# SCH___2021-08-07.net
KiCad netlist of a schematic drawn in EasyEDA
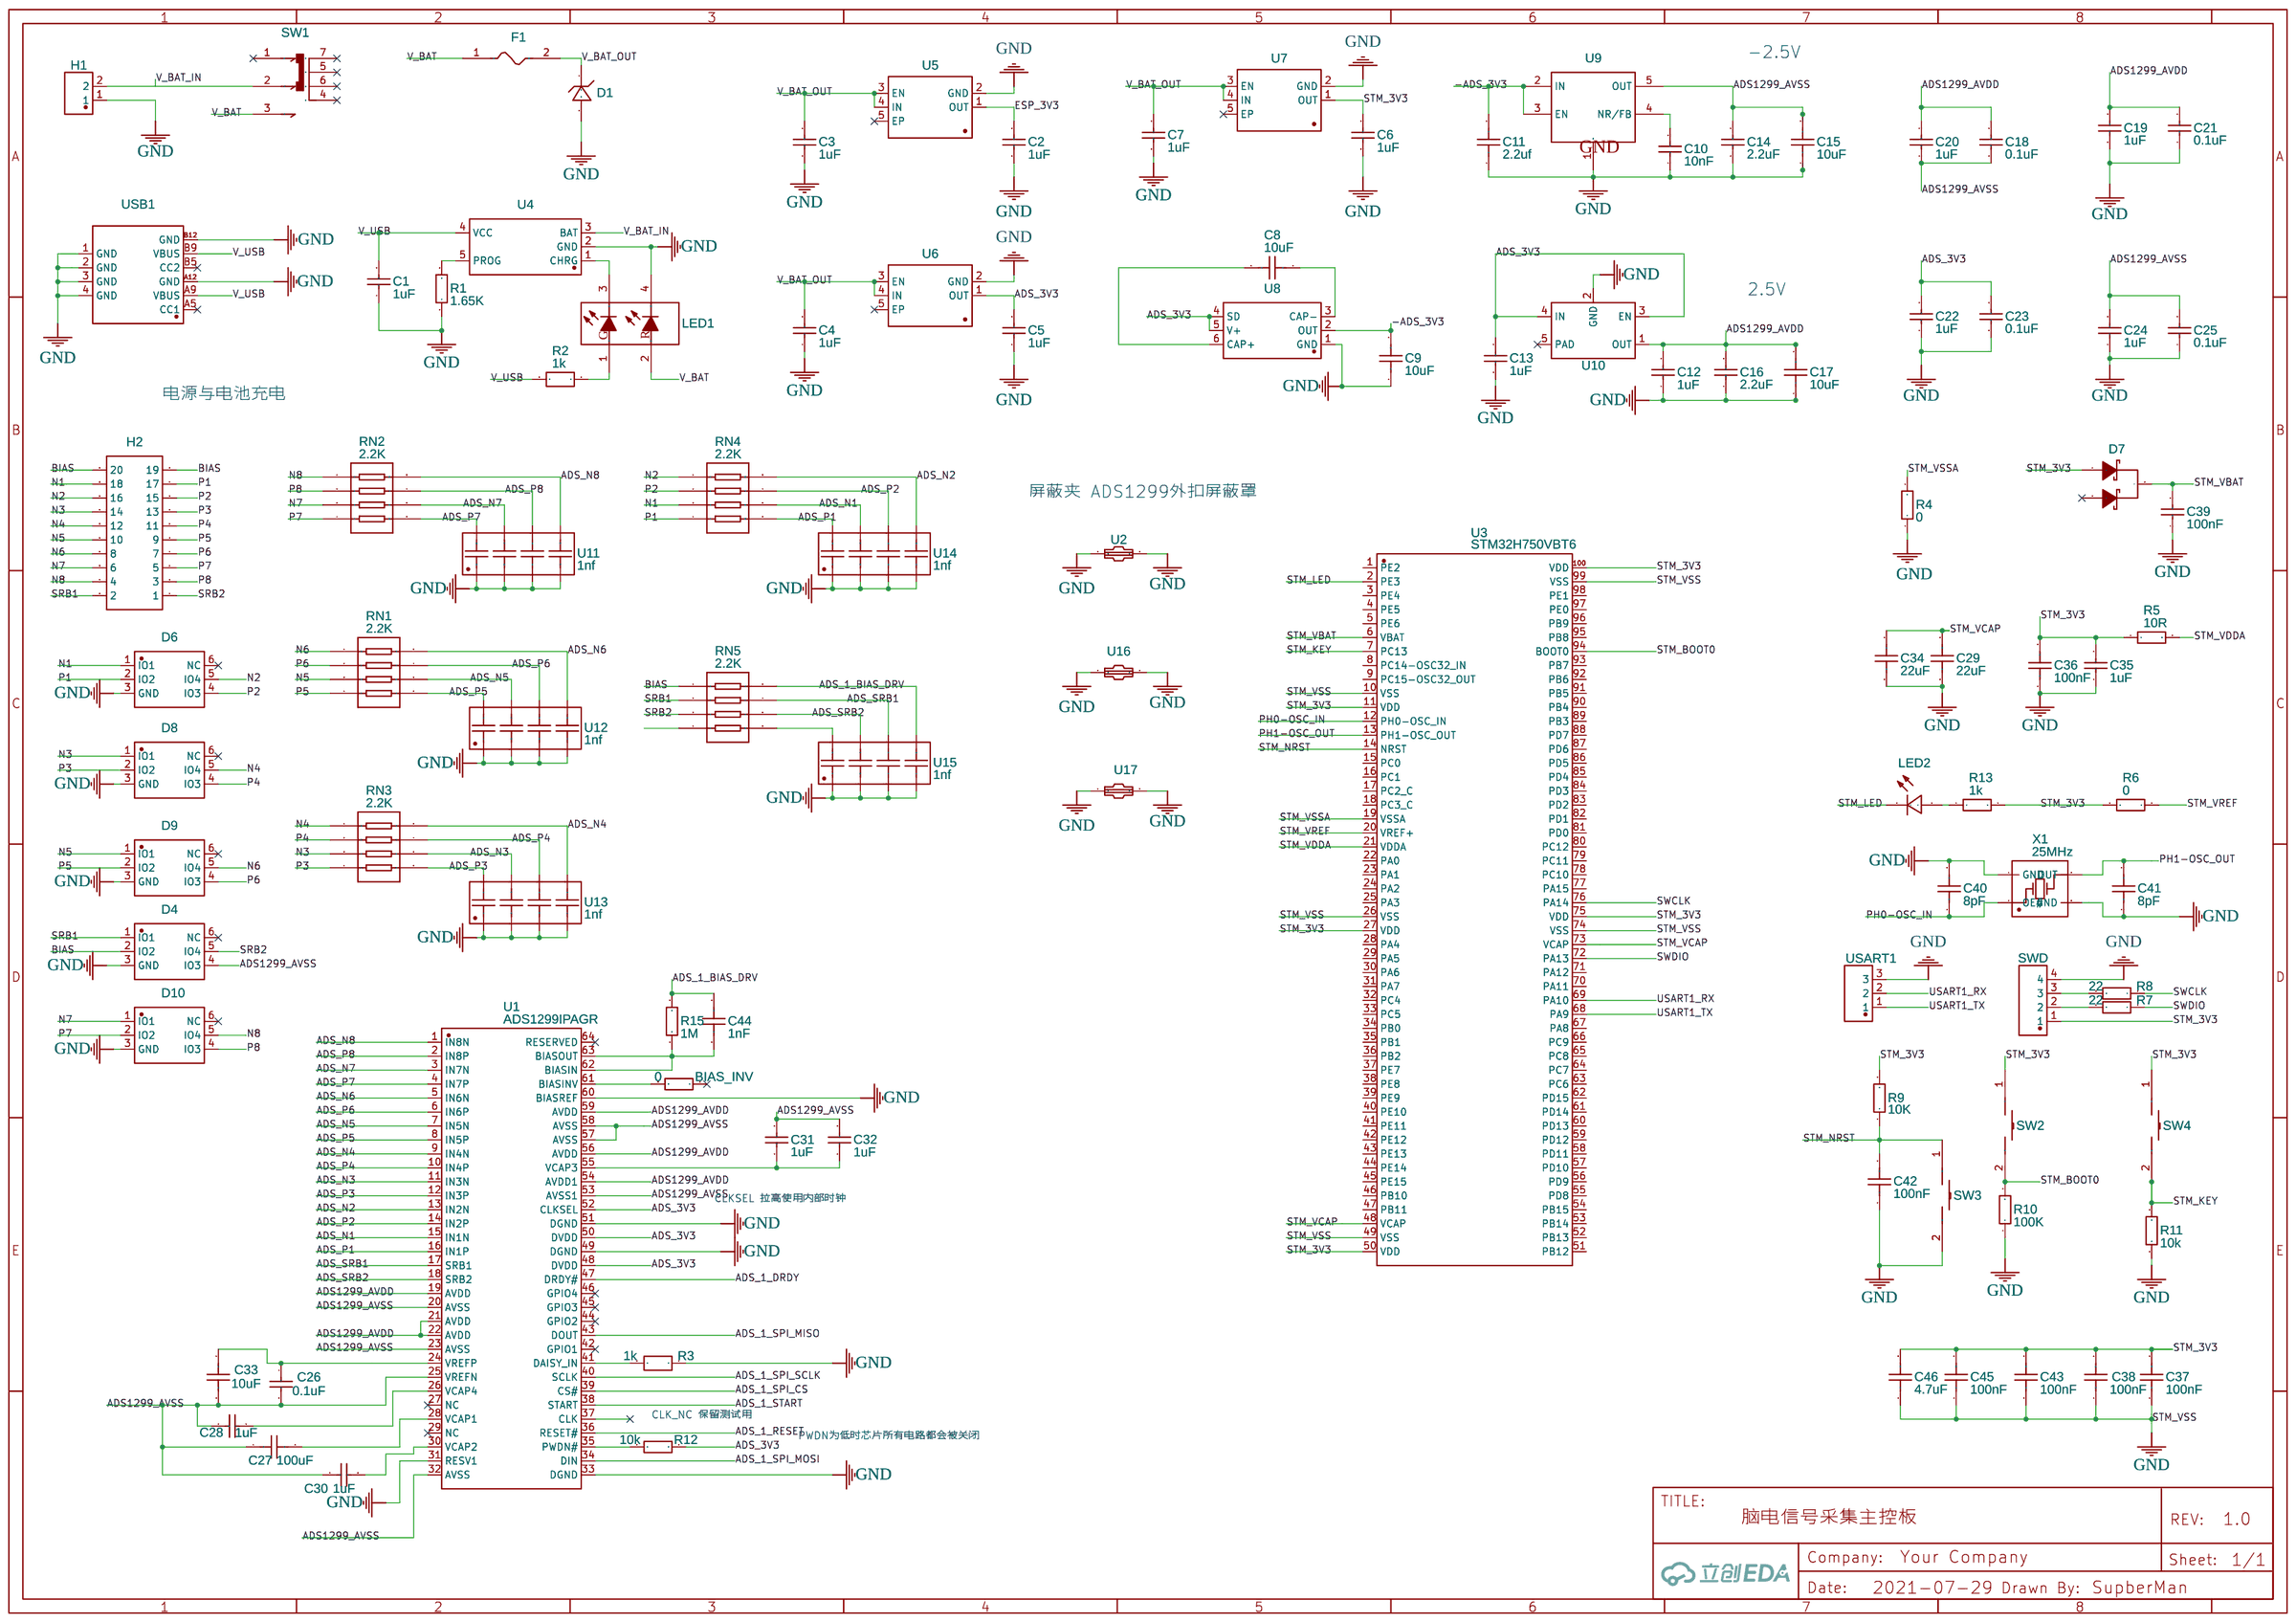
[diagram p0: schematic sheet]

(export (version "E")
  (design (tool "Eeschema 10.0.6"))
  (components
    (comp (ref "BIAS_INV")
      (value "0")
      (fields
        (field (name "BOM_Manufacturer Part") "0402WGJ0000TCE")
        (field (name "BOM_Supplier Part") "C21376")
      )
      (libsource (lib "") (part "0402WGJ0000TCE_3"))
    )
    (comp (ref "C1")
      (value "1uF")
      (fields
        (field (name "BOM_Manufacturer Part") "0603F105M160NT")
        (field (name "BOM_Supplier Part") "C1689")
      )
      (libsource (lib "") (part "0603F105M160NT"))
    )
    (comp (ref "C2")
      (value "1uF")
      (fields
        (field (name "BOM_Manufacturer Part") "0402B105K100NT")
        (field (name "BOM_Supplier Part") "C1526")
      )
      (libsource (lib "") (part "0402B105K100NT"))
    )
    (comp (ref "C3")
      (value "1uF")
      (fields
        (field (name "BOM_Manufacturer Part") "0603F105M160NT")
        (field (name "BOM_Supplier Part") "C1689")
      )
      (libsource (lib "") (part "0603F105M160NT"))
    )
    (comp (ref "C4")
      (value "1uF")
      (fields
        (field (name "BOM_Manufacturer Part") "0603F105M160NT")
        (field (name "BOM_Supplier Part") "C1689")
      )
      (libsource (lib "") (part "0603F105M160NT"))
    )
    (comp (ref "C5")
      (value "1uF")
      (fields
        (field (name "BOM_Manufacturer Part") "0402B105K100NT")
        (field (name "BOM_Supplier Part") "C1526")
      )
      (libsource (lib "") (part "0402B105K100NT"))
    )
    (comp (ref "C6")
      (value "1uF")
      (fields
        (field (name "BOM_Manufacturer Part") "0402B105K100NT")
        (field (name "BOM_Supplier Part") "C1526")
      )
      (libsource (lib "") (part "0402B105K100NT"))
    )
    (comp (ref "C7")
      (value "1uF")
      (fields
        (field (name "BOM_Manufacturer Part") "0603F105M160NT")
        (field (name "BOM_Supplier Part") "C1689")
      )
      (libsource (lib "") (part "0603F105M160NT"))
    )
    (comp (ref "C8")
      (value "10uF")
      (fields
        (field (name "BOM_Manufacturer Part") "GRT188R61E106ME13D")
        (field (name "BOM_Supplier Part") "C697423")
      )
      (libsource (lib "") (part "GRT188R61E106ME13D_1"))
    )
    (comp (ref "C9")
      (value "10uF")
      (fields
        (field (name "BOM_Manufacturer Part") "GRT188R61E106ME13D")
        (field (name "BOM_Supplier Part") "C697423")
      )
      (libsource (lib "") (part "GRT188R61E106ME13D"))
    )
    (comp (ref "C10")
      (value "10nF")
      (fields
        (field (name "BOM_Manufacturer Part") "0402B103K500NT")
        (field (name "BOM_Supplier Part") "C1524")
      )
      (libsource (lib "") (part "0402B103K500NT_1"))
    )
    (comp (ref "C11")
      (value "2.2uf")
      (fields
        (field (name "BOM_Manufacturer Part") "EMK105CC6225KV-F")
        (field (name "BOM_Supplier Part") "C697612")
      )
      (libsource (lib "") (part "EMK105CC6225KV-F"))
    )
    (comp (ref "C12")
      (value "1uF")
      (fields
        (field (name "BOM_Manufacturer Part") "0402B105K100NT")
        (field (name "BOM_Supplier Part") "C1526")
      )
      (libsource (lib "") (part "0402B105K100NT"))
    )
    (comp (ref "C13")
      (value "1uF")
      (fields
        (field (name "BOM_Manufacturer Part") "0402B105K100NT")
        (field (name "BOM_Supplier Part") "C1526")
      )
      (libsource (lib "") (part "0402B105K100NT"))
    )
    (comp (ref "C14")
      (value "2.2uF")
      (fields
        (field (name "BOM_Manufacturer Part") "0402B103K500NT")
        (field (name "BOM_Supplier Part") "C1524")
      )
      (libsource (lib "") (part "0402B103K500NT_1"))
    )
    (comp (ref "C15")
      (value "10uF")
      (fields
        (field (name "BOM_Manufacturer Part") "GRT188R61E106ME13D")
        (field (name "BOM_Supplier Part") "C697423")
      )
      (libsource (lib "") (part "GRT188R61E106ME13D"))
    )
    (comp (ref "C16")
      (value "2.2uF")
      (fields
        (field (name "BOM_Manufacturer Part") "0402B103K500NT")
        (field (name "BOM_Supplier Part") "C1524")
      )
      (libsource (lib "") (part "0402B103K500NT_1"))
    )
    (comp (ref "C17")
      (value "10uF")
      (fields
        (field (name "BOM_Manufacturer Part") "GRT188R61E106ME13D")
        (field (name "BOM_Supplier Part") "C697423")
      )
      (libsource (lib "") (part "GRT188R61E106ME13D"))
    )
    (comp (ref "C18")
      (value "0.1uF")
      (fields
        (field (name "BOM_Manufacturer Part") "0402B103K500NT")
        (field (name "BOM_Supplier Part") "C1524")
      )
      (libsource (lib "") (part "0402B103K500NT_1"))
    )
    (comp (ref "C19")
      (value "1uF")
      (fields
        (field (name "BOM_Manufacturer Part") "0402B103K500NT")
        (field (name "BOM_Supplier Part") "C1524")
      )
      (libsource (lib "") (part "0402B103K500NT_1"))
    )
    (comp (ref "C20")
      (value "1uF")
      (fields
        (field (name "BOM_Manufacturer Part") "0402B103K500NT")
        (field (name "BOM_Supplier Part") "C1524")
      )
      (libsource (lib "") (part "0402B103K500NT_1"))
    )
    (comp (ref "C21")
      (value "0.1uF")
      (fields
        (field (name "BOM_Manufacturer Part") "0402B103K500NT")
        (field (name "BOM_Supplier Part") "C1524")
      )
      (libsource (lib "") (part "0402B103K500NT_1"))
    )
    (comp (ref "C22")
      (value "1uF")
      (fields
        (field (name "BOM_Manufacturer Part") "0402B103K500NT")
        (field (name "BOM_Supplier Part") "C1524")
      )
      (libsource (lib "") (part "0402B103K500NT_1"))
    )
    (comp (ref "C23")
      (value "0.1uF")
      (fields
        (field (name "BOM_Manufacturer Part") "0402B103K500NT")
        (field (name "BOM_Supplier Part") "C1524")
      )
      (libsource (lib "") (part "0402B103K500NT_1"))
    )
    (comp (ref "C24")
      (value "1uF")
      (fields
        (field (name "BOM_Manufacturer Part") "0402B103K500NT")
        (field (name "BOM_Supplier Part") "C1524")
      )
      (libsource (lib "") (part "0402B103K500NT_1"))
    )
    (comp (ref "C25")
      (value "0.1uF")
      (fields
        (field (name "BOM_Manufacturer Part") "0402B103K500NT")
        (field (name "BOM_Supplier Part") "C1524")
      )
      (libsource (lib "") (part "0402B103K500NT_1"))
    )
    (comp (ref "C26")
      (value "0.1uF")
      (fields
        (field (name "BOM_Manufacturer Part") "0402B103K500NT")
        (field (name "BOM_Supplier Part") "C1524")
      )
      (libsource (lib "") (part "0402B103K500NT"))
    )
    (comp (ref "C27")
      (value "100uF")
      (fields
        (field (name "BOM_Manufacturer Part") "1210X107M6R3CT")
        (field (name "BOM_Supplier Part") "C509278")
      )
      (libsource (lib "") (part "1210X107M6R3CT"))
    )
    (comp (ref "C28")
      (value "1uF")
      (fields
        (field (name "BOM_Manufacturer Part") "0402B103K500NT")
        (field (name "BOM_Supplier Part") "C1524")
      )
      (libsource (lib "") (part "0402B103K500NT_2"))
    )
    (comp (ref "C29")
      (value "22uF")
      (fields
        (field (name "BOM_Manufacturer Part") "GRM155R60J226ME11D")
        (field (name "BOM_Supplier Part") "C415703")
      )
      (libsource (lib "") (part "GRM155R60J226ME11D"))
    )
    (comp (ref "C30")
      (value "1uF")
      (fields
        (field (name "BOM_Manufacturer Part") "0402B103K500NT")
        (field (name "BOM_Supplier Part") "C1524")
      )
      (libsource (lib "") (part "0402B103K500NT_2"))
    )
    (comp (ref "C31")
      (value "1uF")
      (fields
        (field (name "BOM_Manufacturer Part") "0402B103K500NT")
        (field (name "BOM_Supplier Part") "C1524")
      )
      (libsource (lib "") (part "0402B103K500NT_1"))
    )
    (comp (ref "C32")
      (value "1uF")
      (fields
        (field (name "BOM_Manufacturer Part") "0402B103K500NT")
        (field (name "BOM_Supplier Part") "C1524")
      )
      (libsource (lib "") (part "0402B103K500NT_1"))
    )
    (comp (ref "C33")
      (value "10uF")
      (fields
        (field (name "BOM_Manufacturer Part") "GRT188R61E106ME13D")
        (field (name "BOM_Supplier Part") "C697423")
      )
      (libsource (lib "") (part "GRT188R61E106ME13D_2"))
    )
    (comp (ref "C34")
      (value "22uF")
      (fields
        (field (name "BOM_Manufacturer Part") "GRM155R60J226ME11D")
        (field (name "BOM_Supplier Part") "C415703")
      )
      (libsource (lib "") (part "GRM155R60J226ME11D"))
    )
    (comp (ref "C35")
      (value "1uF")
      (fields
        (field (name "BOM_Manufacturer Part") "0402B105K100NT")
        (field (name "BOM_Supplier Part") "C1526")
      )
      (libsource (lib "") (part "0402B105K100NT"))
    )
    (comp (ref "C36")
      (value "100nF")
      (fields
        (field (name "BOM_Manufacturer Part") "CC0402KRX7R7BB104")
        (field (name "BOM_Supplier Part") "C60474")
      )
      (libsource (lib "") (part "CC0402KRX7R7BB104"))
    )
    (comp (ref "C37")
      (value "100nF")
      (fields
        (field (name "BOM_Manufacturer Part") "CC0402KRX7R7BB104")
        (field (name "BOM_Supplier Part") "C60474")
      )
      (libsource (lib "") (part "CC0402KRX7R7BB104"))
    )
    (comp (ref "C38")
      (value "100nF")
      (fields
        (field (name "BOM_Manufacturer Part") "CC0402KRX7R7BB104")
        (field (name "BOM_Supplier Part") "C60474")
      )
      (libsource (lib "") (part "CC0402KRX7R7BB104"))
    )
    (comp (ref "C39")
      (value "100nF")
      (fields
        (field (name "BOM_Manufacturer Part") "CL05B104KO5NNNC")
        (field (name "BOM_Supplier Part") "C1525")
      )
      (libsource (lib "") (part "CL05B104KO5NNNC"))
    )
    (comp (ref "C40")
      (value "8pF")
      (fields
        (field (name "BOM_Manufacturer Part") "AC0402DRNPO9BN8R0")
        (field (name "BOM_Supplier Part") "C705009")
      )
      (libsource (lib "") (part "AC0402DRNPO9BN8R0"))
    )
    (comp (ref "C41")
      (value "8pF")
      (fields
        (field (name "BOM_Manufacturer Part") "AC0402DRNPO9BN8R0")
        (field (name "BOM_Supplier Part") "C705009")
      )
      (libsource (lib "") (part "AC0402DRNPO9BN8R0"))
    )
    (comp (ref "C42")
      (value "100nF")
      (fields
        (field (name "BOM_Manufacturer Part") "TMK105BJ104KV-F")
        (field (name "BOM_Supplier Part") "C92826")
      )
      (libsource (lib "") (part "TMK105BJ104KV-F"))
    )
    (comp (ref "C43")
      (value "100nF")
      (fields
        (field (name "BOM_Manufacturer Part") "CC0402KRX7R7BB104")
        (field (name "BOM_Supplier Part") "C60474")
      )
      (libsource (lib "") (part "CC0402KRX7R7BB104"))
    )
    (comp (ref "C44")
      (value "1nF")
      (fields
        (field (name "BOM_Manufacturer Part") "0402YC102KAT2A")
        (field (name "BOM_Supplier Part") "C597052")
      )
      (libsource (lib "") (part "0402YC102KAT2A"))
    )
    (comp (ref "C45")
      (value "100nF")
      (fields
        (field (name "BOM_Manufacturer Part") "CC0402KRX7R7BB104")
        (field (name "BOM_Supplier Part") "C60474")
      )
      (libsource (lib "") (part "CC0402KRX7R7BB104"))
    )
    (comp (ref "C46")
      (value "4.7uF")
      (fields
        (field (name "BOM_Manufacturer Part") "JMK105BC6475MV-F")
        (field (name "BOM_Supplier Part") "C697614")
      )
      (libsource (lib "") (part "JMK105BC6475MV-F"))
    )
    (comp (ref "D1")
      (value "PTVS6V5S1UR")
      (fields (field (name "BOM_Supplier Part") "C85179"))
      (libsource (lib "") (part "PTVS6V5S1UR"))
    )
    (comp (ref "D4")
      (value "TPD4E1B06DCKR")
      (fields (field (name "BOM_Supplier Part") "C840093"))
      (libsource (lib "") (part "TPD4E1B06DCKR"))
    )
    (comp (ref "D6")
      (value "TPD4E1B06DCKR")
      (fields (field (name "BOM_Supplier Part") "C840093"))
      (libsource (lib "") (part "TPD4E1B06DCKR"))
    )
    (comp (ref "D7")
      (value "BAT54C_C556168")
      (fields (field (name "BOM_Manufacturer Part") "BAT54C") (field (name "BOM_Supplier Part") "C556168"))
      (libsource (lib "") (part "BAT54C_C556168"))
    )
    (comp (ref "D8")
      (value "TPD4E1B06DCKR")
      (fields (field (name "BOM_Supplier Part") "C840093"))
      (libsource (lib "") (part "TPD4E1B06DCKR"))
    )
    (comp (ref "D9")
      (value "TPD4E1B06DCKR")
      (fields (field (name "BOM_Supplier Part") "C840093"))
      (libsource (lib "") (part "TPD4E1B06DCKR"))
    )
    (comp (ref "D10")
      (value "TPD4E1B06DCKR")
      (fields (field (name "BOM_Supplier Part") "C840093"))
      (libsource (lib "") (part "TPD4E1B06DCKR"))
    )
    (comp (ref "F1")
      (value "SMD0805-100")
      (fields (field (name "BOM_Supplier Part") "C70061"))
      (libsource (lib "") (part "SMD0805-100"))
    )
    (comp (ref "H1")
      (value "GP26-2520WV-2P")
      (fields (field (name "BOM_Supplier Part") "C2681737"))
      (libsource (lib "") (part "GP26-2520WV-2P"))
    )
    (comp (ref "H2")
      (value "A2541WR-2X10P")
      (fields
        (field (name "BOM_Manufacturer Part") "A2541WR-2x10P")
        (field (name "BOM_Supplier Part") "C239341")
      )
      (libsource (lib "") (part "A2541WR-2X10P"))
    )
    (comp (ref "LED1")
      (value "HSMF-C165")
      (fields (field (name "BOM_Supplier Part") "C188726"))
      (libsource (lib "") (part "HSMF-C165"))
    )
    (comp (ref "LED2")
      (value "D-G060306G1-KS2")
      (fields (field (name "BOM_Supplier Part") "C118334"))
      (libsource (lib "") (part "D-G060306G1-KS2"))
    )
    (comp (ref "R1")
      (value "1.65K")
      (fields
        (field (name "BOM_Manufacturer Part") "RMC06031.65K1%N")
        (field (name "BOM_Supplier Part") "C269417")
      )
      (libsource (lib "") (part "RMC06031.65K1%N"))
    )
    (comp (ref "R2")
      (value "1k")
      (fields
        (field (name "BOM_Manufacturer Part") "CRCW04021K00JNED")
        (field (name "BOM_Supplier Part") "C191588")
      )
      (libsource (lib "") (part "CRCW04021K00JNED"))
    )
    (comp (ref "R3")
      (value "1k")
      (fields
        (field (name "BOM_Manufacturer Part") "CRCW04021K00JNED")
        (field (name "BOM_Supplier Part") "C191588")
      )
      (libsource (lib "") (part "CRCW04021K00JNED"))
    )
    (comp (ref "R4")
      (value "0")
      (fields
        (field (name "BOM_Manufacturer Part") "0402WGJ0000TCE")
        (field (name "BOM_Supplier Part") "C21376")
      )
      (libsource (lib "") (part "0402WGJ0000TCE"))
    )
    (comp (ref "R5")
      (value "10R")
      (fields
        (field (name "BOM_Manufacturer Part") "0402WGJ0000TCE")
        (field (name "BOM_Supplier Part") "C21376")
      )
      (libsource (lib "") (part "0402WGJ0000TCE_1"))
    )
    (comp (ref "R6")
      (value "0")
      (fields
        (field (name "BOM_Manufacturer Part") "0402WGJ0000TCE")
        (field (name "BOM_Supplier Part") "C21376")
      )
      (libsource (lib "") (part "0402WGJ0000TCE_2"))
    )
    (comp (ref "R7")
      (value "22")
      (fields
        (field (name "BOM_Manufacturer Part") "CR0402FF22R0G")
        (field (name "BOM_Supplier Part") "C100318")
      )
      (libsource (lib "") (part "CR0402FF22R0G"))
    )
    (comp (ref "R8")
      (value "22")
      (fields
        (field (name "BOM_Manufacturer Part") "CR0402FF22R0G")
        (field (name "BOM_Supplier Part") "C100318")
      )
      (libsource (lib "") (part "CR0402FF22R0G"))
    )
    (comp (ref "R9")
      (value "10K")
      (fields
        (field (name "BOM_Manufacturer Part") "TR0402D10KQ1025")
        (field (name "BOM_Supplier Part") "C149898")
      )
      (libsource (lib "") (part "TR0402D10KQ1025"))
    )
    (comp (ref "R10")
      (value "100K")
      (fields
        (field (name "BOM_Manufacturer Part") "0402WGJ0000TCE")
        (field (name "BOM_Supplier Part") "C21376")
      )
      (libsource (lib "") (part "0402WGJ0000TCE"))
    )
    (comp (ref "R11")
      (value "10k")
      (fields
        (field (name "BOM_Manufacturer Part") "0402WGJ0000TCE")
        (field (name "BOM_Supplier Part") "C21376")
      )
      (libsource (lib "") (part "0402WGJ0000TCE"))
    )
    (comp (ref "R12")
      (value "10k")
      (fields
        (field (name "BOM_Manufacturer Part") "0402WGJ0000TCE")
        (field (name "BOM_Supplier Part") "C21376")
      )
      (libsource (lib "") (part "0402WGJ0000TCE_2"))
    )
    (comp (ref "R13")
      (value "1k")
      (fields
        (field (name "BOM_Manufacturer Part") "0402WGJ0000TCE")
        (field (name "BOM_Supplier Part") "C21376")
      )
      (libsource (lib "") (part "0402WGJ0000TCE_1"))
    )
    (comp (ref "R15")
      (value "1M")
      (fields
        (field (name "BOM_Manufacturer Part") "MR04X105JTL")
        (field (name "BOM_Supplier Part") "C327805")
      )
      (libsource (lib "") (part "MR04X105JTL"))
    )
    (comp (ref "RN1")
      (value "2.2K")
      (fields
        (field (name "BOM_Manufacturer Part") "4D03WGJ0222T5E")
        (field (name "BOM_Supplier Part") "C12001")
      )
      (libsource (lib "") (part "4D03WGJ0222T5E"))
    )
    (comp (ref "RN2")
      (value "2.2K")
      (fields
        (field (name "BOM_Manufacturer Part") "4D03WGJ0222T5E")
        (field (name "BOM_Supplier Part") "C12001")
      )
      (libsource (lib "") (part "4D03WGJ0222T5E"))
    )
    (comp (ref "RN3")
      (value "2.2K")
      (fields
        (field (name "BOM_Manufacturer Part") "4D03WGJ0222T5E")
        (field (name "BOM_Supplier Part") "C12001")
      )
      (libsource (lib "") (part "4D03WGJ0222T5E"))
    )
    (comp (ref "RN4")
      (value "2.2K")
      (fields
        (field (name "BOM_Manufacturer Part") "4D03WGJ0222T5E")
        (field (name "BOM_Supplier Part") "C12001")
      )
      (libsource (lib "") (part "4D03WGJ0222T5E"))
    )
    (comp (ref "RN5")
      (value "2.2K")
      (fields
        (field (name "BOM_Manufacturer Part") "4D03WGJ0222T5E")
        (field (name "BOM_Supplier Part") "C12001")
      )
      (libsource (lib "") (part "4D03WGJ0222T5E"))
    )
    (comp (ref "SW1")
      (value "TA-3524A-A1-W")
      (fields (field (name "BOM_Supplier Part") "C730329"))
      (libsource (lib "") (part "TA-3524A-A1-W"))
    )
    (comp (ref "SW2")
      (value "MPTFP2-V-T/R")
      (fields (field (name "BOM_Supplier Part") "C495942"))
      (libsource (lib "") (part "MPTFP2-V-T/R"))
    )
    (comp (ref "SW3")
      (value "MPTFP2-V-T/R")
      (fields (field (name "BOM_Supplier Part") "C495942"))
      (libsource (lib "") (part "MPTFP2-V-T/R"))
    )
    (comp (ref "SW4")
      (value "MPTFP2-V-T/R")
      (fields (field (name "BOM_Supplier Part") "C495942"))
      (libsource (lib "") (part "MPTFP2-V-T/R"))
    )
    (comp (ref "SWD")
      (value "12251104CNSNS295001")
      (fields (field (name "BOM_Supplier Part") "C355292"))
      (libsource (lib "") (part "12251104CNSNS295001"))
    )
    (comp (ref "U1")
      (value "ADS1299IPAGR")
      (fields (field (name "BOM_Supplier Part") "C476817"))
      (libsource (lib "") (part "ADS1299IPAGR"))
    )
    (comp (ref "U2")
      (value "ICSRC3910SFR")
      (fields (field (name "BOM_Supplier Part") "C238204"))
      (libsource (lib "") (part "ICSRC3910SFR"))
    )
    (comp (ref "U3")
      (value "STM32H750VBT6")
      (fields (field (name "BOM_Supplier Part") "C404010"))
      (libsource (lib "") (part "STM32H750VBT6"))
    )
    (comp (ref "U4")
      (value "ME4074AM5G")
      (fields (field (name "BOM_Supplier Part") "C236729"))
      (libsource (lib "") (part "ME4074AM5G"))
    )
    (comp (ref "U5")
      (value "LP5907SNX-3.3/NOPB")
      (fields (field (name "BOM_Supplier Part") "C133572"))
      (libsource (lib "") (part "LP5907SNX-3.3/NOPB"))
    )
    (comp (ref "U6")
      (value "LP5907SNX-3.3/NOPB")
      (fields (field (name "BOM_Supplier Part") "C133572"))
      (libsource (lib "") (part "LP5907SNX-3.3/NOPB"))
    )
    (comp (ref "U7")
      (value "LP5907SNX-3.3/NOPB")
      (fields (field (name "BOM_Supplier Part") "C133572"))
      (libsource (lib "") (part "LP5907SNX-3.3/NOPB"))
    )
    (comp (ref "U8")
      (value "LM2664M6/NOPB")
      (fields (field (name "BOM_Supplier Part") "C840095"))
      (libsource (lib "") (part "LM2664M6/NOPB"))
    )
    (comp (ref "U9")
      (value "TPS72325DBVR")
      (fields (field (name "BOM_Supplier Part") "C69932"))
      (libsource (lib "") (part "TPS72325DBVR"))
    )
    (comp (ref "U10")
      (value "LP5907SNX-2.5NOPB")
      (fields (field (name "BOM_Supplier Part") "C133571"))
      (libsource (lib "") (part "LP5907SNX-2.5NOPB"))
    )
    (comp (ref "U11")
      (value "1nf")
      (fields
        (field (name "BOM_Manufacturer Part") "CKCA43X7R1H102MT010N")
        (field (name "BOM_Supplier Part") "C338043")
      )
      (libsource (lib "") (part "CKCA43X7R1H102MT010N"))
    )
    (comp (ref "U12")
      (value "1nf")
      (fields
        (field (name "BOM_Manufacturer Part") "CKCA43X7R1H102MT010N")
        (field (name "BOM_Supplier Part") "C338043")
      )
      (libsource (lib "") (part "CKCA43X7R1H102MT010N"))
    )
    (comp (ref "U13")
      (value "1nf")
      (fields
        (field (name "BOM_Manufacturer Part") "CKCA43X7R1H102MT010N")
        (field (name "BOM_Supplier Part") "C338043")
      )
      (libsource (lib "") (part "CKCA43X7R1H102MT010N"))
    )
    (comp (ref "U14")
      (value "1nf")
      (fields
        (field (name "BOM_Manufacturer Part") "CKCA43X7R1H102MT010N")
        (field (name "BOM_Supplier Part") "C338043")
      )
      (libsource (lib "") (part "CKCA43X7R1H102MT010N"))
    )
    (comp (ref "U15")
      (value "1nf")
      (fields
        (field (name "BOM_Manufacturer Part") "CKCA43X7R1H102MT010N")
        (field (name "BOM_Supplier Part") "C338043")
      )
      (libsource (lib "") (part "CKCA43X7R1H102MT010N"))
    )
    (comp (ref "U16")
      (value "ICSRC3910SFR")
      (fields (field (name "BOM_Supplier Part") "C238204"))
      (libsource (lib "") (part "ICSRC3910SFR"))
    )
    (comp (ref "U17")
      (value "ICSRC3910SFR")
      (fields (field (name "BOM_Supplier Part") "C238204"))
      (libsource (lib "") (part "ICSRC3910SFR"))
    )
    (comp (ref "USART1")
      (value "22032031")
      (fields (field (name "BOM_Supplier Part") "C505002"))
      (libsource (lib "") (part "22032031"))
    )
    (comp (ref "USB1")
      (value "TYPEC-250D-BCP6")
      (fields (field (name "BOM_Supplier Part") "C720626"))
      (libsource (lib "") (part "TYPEC-250D-BCP6"))
    )
    (comp (ref "X1")
      (value "25MHz")
      (fields
        (field (name "BOM_Manufacturer Part") "Q22FA1280056900")
        (field (name "BOM_Supplier Part") "C193187")
      )
      (libsource (lib "") (part "Q22FA1280056900"))
    )
  )
  (nets
    (net (code "1") (name "/-ADS_3V3") (class "Default")
      (node (ref "C11") (pin "2") (pinfunction "2_2") (pintype "unspecified"))
      (node (ref "C9") (pin "2") (pinfunction "2_2") (pintype "unspecified"))
      (node (ref "U8") (pin "2") (pinfunction "OUT_2") (pintype "unspecified"))
      (node (ref "U9") (pin "2") (pinfunction "IN_2") (pintype "passive"))
      (node (ref "U9") (pin "3") (pinfunction "EN_3") (pintype "unspecified"))
    )
    (net (code "2") (name "/ADS1299_AVDD") (class "Default")
      (node (ref "C12") (pin "2") (pinfunction "2_2") (pintype "input"))
      (node (ref "C16") (pin "2") (pinfunction "2_2") (pintype "input"))
      (node (ref "C17") (pin "2") (pinfunction "2_2") (pintype "unspecified"))
      (node (ref "C18") (pin "2") (pinfunction "2_2") (pintype "input"))
      (node (ref "C19") (pin "2") (pinfunction "2_2") (pintype "input"))
      (node (ref "C20") (pin "2") (pinfunction "2_2") (pintype "input"))
      (node (ref "C21") (pin "2") (pinfunction "2_2") (pintype "input"))
      (node (ref "U1") (pin "19") (pinfunction "AVDD_19") (pintype "unspecified"))
      (node (ref "U1") (pin "21") (pinfunction "AVDD_21") (pintype "unspecified"))
      (node (ref "U1") (pin "22") (pinfunction "AVDD_22") (pintype "unspecified"))
      (node (ref "U1") (pin "54") (pinfunction "AVDD1_54") (pintype "unspecified"))
      (node (ref "U1") (pin "56") (pinfunction "AVDD_56") (pintype "unspecified"))
      (node (ref "U1") (pin "59") (pinfunction "AVDD_59") (pintype "unspecified"))
      (node (ref "U10") (pin "1") (pinfunction "OUT_1") (pintype "unspecified"))
    )
    (net (code "3") (name "/ADS1299_AVSS") (class "Default")
      (node (ref "C14") (pin "2") (pinfunction "2_2") (pintype "input"))
      (node (ref "C15") (pin "2") (pinfunction "2_2") (pintype "unspecified"))
      (node (ref "C18") (pin "1") (pinfunction "1_1") (pintype "input"))
      (node (ref "C20") (pin "1") (pinfunction "1_1") (pintype "input"))
      (node (ref "C24") (pin "2") (pinfunction "2_2") (pintype "input"))
      (node (ref "C25") (pin "2") (pinfunction "2_2") (pintype "input"))
      (node (ref "C26") (pin "2") (pinfunction "2_2") (pintype "input"))
      (node (ref "C27") (pin "1") (pinfunction "1_1") (pintype "unspecified"))
      (node (ref "C28") (pin "1") (pinfunction "1_1") (pintype "input"))
      (node (ref "C30") (pin "1") (pinfunction "1_1") (pintype "input"))
      (node (ref "C31") (pin "2") (pinfunction "2_2") (pintype "input"))
      (node (ref "C32") (pin "2") (pinfunction "2_2") (pintype "input"))
      (node (ref "C33") (pin "2") (pinfunction "2_2") (pintype "unspecified"))
      (node (ref "D4") (pin "4") (pinfunction "IO3_4") (pintype "unspecified"))
      (node (ref "U1") (pin "20") (pinfunction "AVSS_20") (pintype "unspecified"))
      (node (ref "U1") (pin "23") (pinfunction "AVSS_23") (pintype "unspecified"))
      (node (ref "U1") (pin "25") (pinfunction "VREFN_25") (pintype "unspecified"))
      (node (ref "U1") (pin "32") (pinfunction "AVSS_32") (pintype "unspecified"))
      (node (ref "U1") (pin "53") (pinfunction "AVSS1_53") (pintype "unspecified"))
      (node (ref "U1") (pin "57") (pinfunction "AVSS_57") (pintype "unspecified"))
      (node (ref "U1") (pin "58") (pinfunction "AVSS_58") (pintype "unspecified"))
      (node (ref "U9") (pin "5") (pinfunction "OUT_5") (pintype "passive"))
    )
    (net (code "4") (name "/ADS_1_BIAS_DRV") (class "Default")
      (node (ref "C44") (pin "1") (pinfunction "1_1") (pintype "unspecified"))
      (node (ref "R15") (pin "2") (pinfunction "2_2") (pintype "unspecified"))
      (node (ref "RN5") (pin "8") (pinfunction "8_8") (pintype "input"))
      (node (ref "U15") (pin "5") (pinfunction "5_5") (pintype "unspecified"))
    )
    (net (code "5") (name "/ADS_1_DRDY") (class "Default")
      (node (ref "U1") (pin "47") (pinfunction "DRDY#_47") (pintype "unspecified"))
    )
    (net (code "6") (name "/ADS_1_RESET") (class "Default")
      (node (ref "U1") (pin "36") (pinfunction "RESET#_36") (pintype "unspecified"))
    )
    (net (code "7") (name "/ADS_1_SPI_CS") (class "Default")
      (node (ref "U1") (pin "39") (pinfunction "CS#_39") (pintype "unspecified"))
    )
    (net (code "8") (name "/ADS_1_SPI_MISO") (class "Default")
      (node (ref "U1") (pin "43") (pinfunction "DOUT_43") (pintype "unspecified"))
    )
    (net (code "9") (name "/ADS_1_SPI_MOSI") (class "Default")
      (node (ref "U1") (pin "34") (pinfunction "DIN_34") (pintype "unspecified"))
    )
    (net (code "10") (name "/ADS_1_SPI_SCLK") (class "Default")
      (node (ref "U1") (pin "40") (pinfunction "SCLK_40") (pintype "unspecified"))
    )
    (net (code "11") (name "/ADS_1_START") (class "Default")
      (node (ref "U1") (pin "38") (pinfunction "START_38") (pintype "unspecified"))
    )
    (net (code "12") (name "/ADS_3V3") (class "Default")
      (node (ref "C13") (pin "2") (pinfunction "2_2") (pintype "input"))
      (node (ref "C22") (pin "2") (pinfunction "2_2") (pintype "input"))
      (node (ref "C23") (pin "2") (pinfunction "2_2") (pintype "input"))
      (node (ref "C5") (pin "2") (pinfunction "2_2") (pintype "input"))
      (node (ref "R12") (pin "1") (pinfunction "1_1") (pintype "input"))
      (node (ref "U1") (pin "48") (pinfunction "DVDD_48") (pintype "unspecified"))
      (node (ref "U1") (pin "50") (pinfunction "DVDD_50") (pintype "unspecified"))
      (node (ref "U1") (pin "52") (pinfunction "CLKSEL_52") (pintype "unspecified"))
      (node (ref "U10") (pin "3") (pinfunction "EN_3") (pintype "unspecified"))
      (node (ref "U10") (pin "4") (pinfunction "IN_4") (pintype "unspecified"))
      (node (ref "U6") (pin "1") (pinfunction "OUT_1") (pintype "unspecified"))
      (node (ref "U8") (pin "4") (pinfunction "SD_4") (pintype "unspecified"))
      (node (ref "U8") (pin "5") (pinfunction "V+_5") (pintype "unspecified"))
    )
    (net (code "13") (name "/ADS_N1") (class "Default")
      (node (ref "RN4") (pin "6") (pinfunction "6_6") (pintype "input"))
      (node (ref "U1") (pin "15") (pinfunction "IN1N_15") (pintype "unspecified"))
      (node (ref "U14") (pin "7") (pinfunction "7_7") (pintype "unspecified"))
    )
    (net (code "14") (name "/ADS_N2") (class "Default")
      (node (ref "RN4") (pin "8") (pinfunction "8_8") (pintype "input"))
      (node (ref "U1") (pin "13") (pinfunction "IN2N_13") (pintype "unspecified"))
      (node (ref "U14") (pin "5") (pinfunction "5_5") (pintype "unspecified"))
    )
    (net (code "15") (name "/ADS_N3") (class "Default")
      (node (ref "RN3") (pin "6") (pinfunction "6_6") (pintype "input"))
      (node (ref "U1") (pin "11") (pinfunction "IN3N_11") (pintype "unspecified"))
      (node (ref "U13") (pin "7") (pinfunction "7_7") (pintype "unspecified"))
    )
    (net (code "16") (name "/ADS_N4") (class "Default")
      (node (ref "RN3") (pin "8") (pinfunction "8_8") (pintype "input"))
      (node (ref "U1") (pin "9") (pinfunction "IN4N_9") (pintype "unspecified"))
      (node (ref "U13") (pin "5") (pinfunction "5_5") (pintype "unspecified"))
    )
    (net (code "17") (name "/ADS_N5") (class "Default")
      (node (ref "RN1") (pin "6") (pinfunction "6_6") (pintype "input"))
      (node (ref "U1") (pin "7") (pinfunction "IN5N_7") (pintype "unspecified"))
      (node (ref "U12") (pin "7") (pinfunction "7_7") (pintype "unspecified"))
    )
    (net (code "18") (name "/ADS_N6") (class "Default")
      (node (ref "RN1") (pin "8") (pinfunction "8_8") (pintype "input"))
      (node (ref "U1") (pin "5") (pinfunction "IN6N_5") (pintype "unspecified"))
      (node (ref "U12") (pin "5") (pinfunction "5_5") (pintype "unspecified"))
    )
    (net (code "19") (name "/ADS_N7") (class "Default")
      (node (ref "RN2") (pin "6") (pinfunction "6_6") (pintype "input"))
      (node (ref "U1") (pin "3") (pinfunction "IN7N_3") (pintype "unspecified"))
      (node (ref "U11") (pin "7") (pinfunction "7_7") (pintype "unspecified"))
    )
    (net (code "20") (name "/ADS_N8") (class "Default")
      (node (ref "RN2") (pin "8") (pinfunction "8_8") (pintype "input"))
      (node (ref "U1") (pin "1") (pinfunction "IN8N_1") (pintype "unspecified"))
      (node (ref "U11") (pin "5") (pinfunction "5_5") (pintype "unspecified"))
    )
    (net (code "21") (name "/ADS_P1") (class "Default")
      (node (ref "RN4") (pin "5") (pinfunction "5_5") (pintype "input"))
      (node (ref "U1") (pin "16") (pinfunction "IN1P_16") (pintype "unspecified"))
      (node (ref "U14") (pin "8") (pinfunction "8_8") (pintype "unspecified"))
    )
    (net (code "22") (name "/ADS_P2") (class "Default")
      (node (ref "RN4") (pin "7") (pinfunction "7_7") (pintype "input"))
      (node (ref "U1") (pin "14") (pinfunction "IN2P_14") (pintype "unspecified"))
      (node (ref "U14") (pin "6") (pinfunction "6_6") (pintype "unspecified"))
    )
    (net (code "23") (name "/ADS_P3") (class "Default")
      (node (ref "RN3") (pin "5") (pinfunction "5_5") (pintype "input"))
      (node (ref "U1") (pin "12") (pinfunction "IN3P_12") (pintype "unspecified"))
      (node (ref "U13") (pin "8") (pinfunction "8_8") (pintype "unspecified"))
    )
    (net (code "24") (name "/ADS_P4") (class "Default")
      (node (ref "RN3") (pin "7") (pinfunction "7_7") (pintype "input"))
      (node (ref "U1") (pin "10") (pinfunction "IN4P_10") (pintype "unspecified"))
      (node (ref "U13") (pin "6") (pinfunction "6_6") (pintype "unspecified"))
    )
    (net (code "25") (name "/ADS_P5") (class "Default")
      (node (ref "RN1") (pin "5") (pinfunction "5_5") (pintype "input"))
      (node (ref "U1") (pin "8") (pinfunction "IN5P_8") (pintype "unspecified"))
      (node (ref "U12") (pin "8") (pinfunction "8_8") (pintype "unspecified"))
    )
    (net (code "26") (name "/ADS_P6") (class "Default")
      (node (ref "RN1") (pin "7") (pinfunction "7_7") (pintype "input"))
      (node (ref "U1") (pin "6") (pinfunction "IN6P_6") (pintype "unspecified"))
      (node (ref "U12") (pin "6") (pinfunction "6_6") (pintype "unspecified"))
    )
    (net (code "27") (name "/ADS_P7") (class "Default")
      (node (ref "RN2") (pin "5") (pinfunction "5_5") (pintype "input"))
      (node (ref "U1") (pin "4") (pinfunction "IN7P_4") (pintype "unspecified"))
      (node (ref "U11") (pin "8") (pinfunction "8_8") (pintype "unspecified"))
    )
    (net (code "28") (name "/ADS_P8") (class "Default")
      (node (ref "RN2") (pin "7") (pinfunction "7_7") (pintype "input"))
      (node (ref "U1") (pin "2") (pinfunction "IN8P_2") (pintype "unspecified"))
      (node (ref "U11") (pin "6") (pinfunction "6_6") (pintype "unspecified"))
    )
    (net (code "29") (name "/ADS_SRB1") (class "Default")
      (node (ref "RN5") (pin "7") (pinfunction "7_7") (pintype "input"))
      (node (ref "U1") (pin "17") (pinfunction "SRB1_17") (pintype "unspecified"))
      (node (ref "U15") (pin "6") (pinfunction "6_6") (pintype "unspecified"))
    )
    (net (code "30") (name "/ADS_SRB2") (class "Default")
      (node (ref "RN5") (pin "6") (pinfunction "6_6") (pintype "input"))
      (node (ref "U1") (pin "18") (pinfunction "SRB2_18") (pintype "unspecified"))
      (node (ref "U15") (pin "7") (pinfunction "7_7") (pintype "unspecified"))
    )
    (net (code "31") (name "/BIAS") (class "Default")
      (node (ref "D4") (pin "2") (pinfunction "IO2_2") (pintype "unspecified"))
      (node (ref "H2") (pin "19") (pinfunction "19_19") (pintype "unspecified"))
      (node (ref "H2") (pin "20") (pinfunction "20_20") (pintype "unspecified"))
      (node (ref "RN5") (pin "1") (pinfunction "1_1") (pintype "input"))
    )
    (net (code "32") (name "/ESP_3V3") (class "Default")
      (node (ref "C2") (pin "2") (pinfunction "2_2") (pintype "input"))
      (node (ref "U5") (pin "1") (pinfunction "OUT_1") (pintype "unspecified"))
    )
    (net (code "33") (name "/N1") (class "Default")
      (node (ref "D6") (pin "1") (pinfunction "IO1_1") (pintype "unspecified"))
      (node (ref "H2") (pin "18") (pinfunction "18_18") (pintype "unspecified"))
      (node (ref "RN4") (pin "3") (pinfunction "3_3") (pintype "input"))
    )
    (net (code "34") (name "/N2") (class "Default")
      (node (ref "D6") (pin "5") (pinfunction "IO4_5") (pintype "unspecified"))
      (node (ref "H2") (pin "16") (pinfunction "16_16") (pintype "unspecified"))
      (node (ref "RN4") (pin "1") (pinfunction "1_1") (pintype "input"))
    )
    (net (code "35") (name "/N3") (class "Default")
      (node (ref "D8") (pin "1") (pinfunction "IO1_1") (pintype "unspecified"))
      (node (ref "H2") (pin "14") (pinfunction "14_14") (pintype "unspecified"))
      (node (ref "RN3") (pin "3") (pinfunction "3_3") (pintype "input"))
    )
    (net (code "36") (name "/N4") (class "Default")
      (node (ref "D8") (pin "5") (pinfunction "IO4_5") (pintype "unspecified"))
      (node (ref "H2") (pin "12") (pinfunction "12_12") (pintype "unspecified"))
      (node (ref "RN3") (pin "1") (pinfunction "1_1") (pintype "input"))
    )
    (net (code "37") (name "/N5") (class "Default")
      (node (ref "D9") (pin "1") (pinfunction "IO1_1") (pintype "unspecified"))
      (node (ref "H2") (pin "10") (pinfunction "10_10") (pintype "unspecified"))
      (node (ref "RN1") (pin "3") (pinfunction "3_3") (pintype "input"))
    )
    (net (code "38") (name "/N6") (class "Default")
      (node (ref "D9") (pin "5") (pinfunction "IO4_5") (pintype "unspecified"))
      (node (ref "H2") (pin "8") (pinfunction "8_8") (pintype "unspecified"))
      (node (ref "RN1") (pin "1") (pinfunction "1_1") (pintype "input"))
    )
    (net (code "39") (name "/N7") (class "Default")
      (node (ref "D10") (pin "1") (pinfunction "IO1_1") (pintype "unspecified"))
      (node (ref "H2") (pin "6") (pinfunction "6_6") (pintype "unspecified"))
      (node (ref "RN2") (pin "3") (pinfunction "3_3") (pintype "input"))
    )
    (net (code "40") (name "/N8") (class "Default")
      (node (ref "D10") (pin "5") (pinfunction "IO4_5") (pintype "unspecified"))
      (node (ref "H2") (pin "4") (pinfunction "4_4") (pintype "unspecified"))
      (node (ref "RN2") (pin "1") (pinfunction "1_1") (pintype "input"))
    )
    (net (code "41") (name "/P1") (class "Default")
      (node (ref "D6") (pin "2") (pinfunction "IO2_2") (pintype "unspecified"))
      (node (ref "H2") (pin "17") (pinfunction "17_17") (pintype "unspecified"))
      (node (ref "RN4") (pin "4") (pinfunction "4_4") (pintype "input"))
    )
    (net (code "42") (name "/P2") (class "Default")
      (node (ref "D6") (pin "4") (pinfunction "IO3_4") (pintype "unspecified"))
      (node (ref "H2") (pin "15") (pinfunction "15_15") (pintype "unspecified"))
      (node (ref "RN4") (pin "2") (pinfunction "2_2") (pintype "input"))
    )
    (net (code "43") (name "/P3") (class "Default")
      (node (ref "D8") (pin "2") (pinfunction "IO2_2") (pintype "unspecified"))
      (node (ref "H2") (pin "13") (pinfunction "13_13") (pintype "unspecified"))
      (node (ref "RN3") (pin "4") (pinfunction "4_4") (pintype "input"))
    )
    (net (code "44") (name "/P4") (class "Default")
      (node (ref "D8") (pin "4") (pinfunction "IO3_4") (pintype "unspecified"))
      (node (ref "H2") (pin "11") (pinfunction "11_11") (pintype "unspecified"))
      (node (ref "RN3") (pin "2") (pinfunction "2_2") (pintype "input"))
    )
    (net (code "45") (name "/P5") (class "Default")
      (node (ref "D9") (pin "2") (pinfunction "IO2_2") (pintype "unspecified"))
      (node (ref "H2") (pin "9") (pinfunction "9_9") (pintype "unspecified"))
      (node (ref "RN1") (pin "4") (pinfunction "4_4") (pintype "input"))
    )
    (net (code "46") (name "/P6") (class "Default")
      (node (ref "D9") (pin "4") (pinfunction "IO3_4") (pintype "unspecified"))
      (node (ref "H2") (pin "7") (pinfunction "7_7") (pintype "unspecified"))
      (node (ref "RN1") (pin "2") (pinfunction "2_2") (pintype "input"))
    )
    (net (code "47") (name "/P7") (class "Default")
      (node (ref "D10") (pin "2") (pinfunction "IO2_2") (pintype "unspecified"))
      (node (ref "H2") (pin "5") (pinfunction "5_5") (pintype "unspecified"))
      (node (ref "RN2") (pin "4") (pinfunction "4_4") (pintype "input"))
    )
    (net (code "48") (name "/P8") (class "Default")
      (node (ref "D10") (pin "4") (pinfunction "IO3_4") (pintype "unspecified"))
      (node (ref "H2") (pin "3") (pinfunction "3_3") (pintype "unspecified"))
      (node (ref "RN2") (pin "2") (pinfunction "2_2") (pintype "input"))
    )
    (net (code "49") (name "/PH0-OSC_IN") (class "Default")
      (node (ref "C40") (pin "1") (pinfunction "1_1") (pintype "unspecified"))
      (node (ref "U3") (pin "12") (pinfunction "PH0-OSC_IN_12") (pintype "unspecified"))
      (node (ref "X1") (pin "1") (pinfunction "OE#_1") (pintype "input"))
    )
    (net (code "50") (name "/PH1-OSC_OUT") (class "Default")
      (node (ref "C41") (pin "2") (pinfunction "2_2") (pintype "unspecified"))
      (node (ref "U3") (pin "13") (pinfunction "PH1-OSC_OUT_13") (pintype "unspecified"))
      (node (ref "X1") (pin "3") (pinfunction "OUT_3") (pintype "input"))
    )
    (net (code "51") (name "/SRB1") (class "Default")
      (node (ref "D4") (pin "1") (pinfunction "IO1_1") (pintype "unspecified"))
      (node (ref "H2") (pin "2") (pinfunction "2_2") (pintype "unspecified"))
      (node (ref "RN5") (pin "2") (pinfunction "2_2") (pintype "input"))
    )
    (net (code "52") (name "/SRB2") (class "Default")
      (node (ref "D4") (pin "5") (pinfunction "IO4_5") (pintype "unspecified"))
      (node (ref "H2") (pin "1") (pinfunction "1_1") (pintype "unspecified"))
      (node (ref "RN5") (pin "3") (pinfunction "3_3") (pintype "input"))
    )
    (net (code "53") (name "/STM_3V3") (class "Default")
      (node (ref "C35") (pin "2") (pinfunction "2_2") (pintype "input"))
      (node (ref "C36") (pin "2") (pinfunction "2_2") (pintype "unspecified"))
      (node (ref "C37") (pin "2") (pinfunction "2_2") (pintype "unspecified"))
      (node (ref "C38") (pin "2") (pinfunction "2_2") (pintype "unspecified"))
      (node (ref "C43") (pin "2") (pinfunction "2_2") (pintype "unspecified"))
      (node (ref "C45") (pin "2") (pinfunction "2_2") (pintype "unspecified"))
      (node (ref "C46") (pin "2") (pinfunction "2_2") (pintype "unspecified"))
      (node (ref "C6") (pin "2") (pinfunction "2_2") (pintype "input"))
      (node (ref "D7") (pin "1") (pinfunction "+_1") (pintype "unspecified"))
      (node (ref "R13") (pin "2") (pinfunction "2_2") (pintype "input"))
      (node (ref "R5") (pin "1") (pinfunction "1_1") (pintype "input"))
      (node (ref "R6") (pin "2") (pinfunction "2_2") (pintype "input"))
      (node (ref "R9") (pin "2") (pinfunction "2_2") (pintype "unspecified"))
      (node (ref "SW2") (pin "1") (pinfunction "1_1") (pintype "unspecified"))
      (node (ref "SW4") (pin "1") (pinfunction "1_1") (pintype "unspecified"))
      (node (ref "SWD") (pin "1") (pinfunction "1_1") (pintype "unspecified"))
      (node (ref "U3") (pin "100") (pinfunction "VDD_100") (pintype "unspecified"))
      (node (ref "U3") (pin "11") (pinfunction "VDD_11") (pintype "unspecified"))
      (node (ref "U3") (pin "27") (pinfunction "VDD_27") (pintype "unspecified"))
      (node (ref "U3") (pin "50") (pinfunction "VDD_50") (pintype "unspecified"))
      (node (ref "U3") (pin "75") (pinfunction "VDD_75") (pintype "unspecified"))
      (node (ref "U7") (pin "1") (pinfunction "OUT_1") (pintype "unspecified"))
    )
    (net (code "54") (name "/STM_BOOT0") (class "Default")
      (node (ref "R10") (pin "2") (pinfunction "2_2") (pintype "input"))
      (node (ref "SW2") (pin "2") (pinfunction "2_2") (pintype "unspecified"))
      (node (ref "U3") (pin "94") (pinfunction "BOOT0_94") (pintype "unspecified"))
    )
    (net (code "55") (name "/STM_KEY") (class "Default")
      (node (ref "R11") (pin "2") (pinfunction "2_2") (pintype "input"))
      (node (ref "SW4") (pin "2") (pinfunction "2_2") (pintype "unspecified"))
      (node (ref "U3") (pin "7") (pinfunction "PC13_7") (pintype "unspecified"))
    )
    (net (code "56") (name "/STM_LED") (class "Default")
      (node (ref "LED2") (pin "1") (pinfunction "-_1") (pintype "unspecified"))
      (node (ref "U3") (pin "2") (pinfunction "PE3_2") (pintype "unspecified"))
    )
    (net (code "57") (name "/STM_NRST") (class "Default")
      (node (ref "C42") (pin "2") (pinfunction "2_2") (pintype "unspecified"))
      (node (ref "R9") (pin "1") (pinfunction "1_1") (pintype "unspecified"))
      (node (ref "SW3") (pin "1") (pinfunction "1_1") (pintype "unspecified"))
      (node (ref "U3") (pin "14") (pinfunction "NRST_14") (pintype "unspecified"))
    )
    (net (code "58") (name "/STM_VBAT") (class "Default")
      (node (ref "C39") (pin "2") (pinfunction "2_2") (pintype "input"))
      (node (ref "D7") (pin "3") (pinfunction "-_3") (pintype "unspecified"))
      (node (ref "U3") (pin "6") (pinfunction "VBAT_6") (pintype "unspecified"))
    )
    (net (code "59") (name "/STM_VCAP") (class "Default")
      (node (ref "C29") (pin "1") (pinfunction "1_1") (pintype "unspecified"))
      (node (ref "C34") (pin "1") (pinfunction "1_1") (pintype "unspecified"))
      (node (ref "U3") (pin "48") (pinfunction "VCAP_48") (pintype "unspecified"))
      (node (ref "U3") (pin "73") (pinfunction "VCAP_73") (pintype "unspecified"))
    )
    (net (code "60") (name "/STM_VDDA") (class "Default")
      (node (ref "R5") (pin "2") (pinfunction "2_2") (pintype "input"))
      (node (ref "U3") (pin "21") (pinfunction "VDDA_21") (pintype "unspecified"))
    )
    (net (code "61") (name "/STM_VREF") (class "Default")
      (node (ref "R6") (pin "1") (pinfunction "1_1") (pintype "input"))
      (node (ref "U3") (pin "20") (pinfunction "VREF+_20") (pintype "unspecified"))
    )
    (net (code "62") (name "/STM_VSSA") (class "Default")
      (node (ref "R4") (pin "2") (pinfunction "2_2") (pintype "input"))
      (node (ref "U3") (pin "19") (pinfunction "VSSA_19") (pintype "unspecified"))
    )
    (net (code "63") (name "/SWCLK") (class "Default")
      (node (ref "R8") (pin "1") (pinfunction "1_1") (pintype "input"))
      (node (ref "U3") (pin "76") (pinfunction "PA14_76") (pintype "unspecified"))
    )
    (net (code "64") (name "/SWDIO") (class "Default")
      (node (ref "R7") (pin "1") (pinfunction "1_1") (pintype "input"))
      (node (ref "U3") (pin "72") (pinfunction "PA13_72") (pintype "unspecified"))
    )
    (net (code "65") (name "/USART1_RX") (class "Default")
      (node (ref "U3") (pin "69") (pinfunction "PA10_69") (pintype "unspecified"))
      (node (ref "USART1") (pin "2") (pinfunction "2_2") (pintype "unspecified"))
    )
    (net (code "66") (name "/USART1_TX") (class "Default")
      (node (ref "U3") (pin "68") (pinfunction "PA9_68") (pintype "unspecified"))
      (node (ref "USART1") (pin "1") (pinfunction "1_1") (pintype "unspecified"))
    )
    (net (code "67") (name "/V_BAT") (class "Default")
      (node (ref "F1") (pin "1") (pinfunction "1_1") (pintype "unspecified"))
      (node (ref "LED1") (pin "2") (pinfunction "A2_2") (pintype "unspecified"))
      (node (ref "SW1") (pin "3") (pinfunction "3_3") (pintype "unspecified"))
    )
    (net (code "68") (name "/V_BAT_IN") (class "Default")
      (node (ref "H1") (pin "2") (pinfunction "2_2") (pintype "unspecified"))
      (node (ref "SW1") (pin "2") (pinfunction "2_2") (pintype "unspecified"))
      (node (ref "U4") (pin "3") (pinfunction "BAT_3") (pintype "unspecified"))
    )
    (net (code "69") (name "/V_BAT_OUT") (class "Default")
      (node (ref "C3") (pin "2") (pinfunction "2_2") (pintype "input"))
      (node (ref "C4") (pin "2") (pinfunction "2_2") (pintype "input"))
      (node (ref "C7") (pin "2") (pinfunction "2_2") (pintype "input"))
      (node (ref "D1") (pin "1") (pinfunction "1_1") (pintype "unspecified"))
      (node (ref "F1") (pin "2") (pinfunction "2_2") (pintype "unspecified"))
      (node (ref "U5") (pin "3") (pinfunction "EN_3") (pintype "unspecified"))
      (node (ref "U5") (pin "4") (pinfunction "IN_4") (pintype "unspecified"))
      (node (ref "U6") (pin "3") (pinfunction "EN_3") (pintype "unspecified"))
      (node (ref "U6") (pin "4") (pinfunction "IN_4") (pintype "unspecified"))
      (node (ref "U7") (pin "3") (pinfunction "EN_3") (pintype "unspecified"))
      (node (ref "U7") (pin "4") (pinfunction "IN_4") (pintype "unspecified"))
    )
    (net (code "70") (name "/V_USB") (class "Default")
      (node (ref "C1") (pin "2") (pinfunction "2_2") (pintype "input"))
      (node (ref "R2") (pin "2") (pinfunction "2_2") (pintype "unspecified"))
      (node (ref "U4") (pin "4") (pinfunction "VCC_4") (pintype "unspecified"))
      (node (ref "USB1") (pin "A9") (pinfunction "VBUS_A9") (pintype "unspecified"))
      (node (ref "USB1") (pin "B9") (pinfunction "VBUS_B9") (pintype "unspecified"))
    )
    (net (code "71") (name "GND") (class "Default")
      (node (ref "C1") (pin "1") (pinfunction "1_1") (pintype "input"))
      (node (ref "C10") (pin "1") (pinfunction "1_1") (pintype "input"))
      (node (ref "C11") (pin "1") (pinfunction "1_1") (pintype "unspecified"))
      (node (ref "C12") (pin "1") (pinfunction "1_1") (pintype "input"))
      (node (ref "C13") (pin "1") (pinfunction "1_1") (pintype "input"))
      (node (ref "C14") (pin "1") (pinfunction "1_1") (pintype "input"))
      (node (ref "C15") (pin "1") (pinfunction "1_1") (pintype "unspecified"))
      (node (ref "C16") (pin "1") (pinfunction "1_1") (pintype "input"))
      (node (ref "C17") (pin "1") (pinfunction "1_1") (pintype "unspecified"))
      (node (ref "C19") (pin "1") (pinfunction "1_1") (pintype "input"))
      (node (ref "C2") (pin "1") (pinfunction "1_1") (pintype "input"))
      (node (ref "C21") (pin "1") (pinfunction "1_1") (pintype "input"))
      (node (ref "C22") (pin "1") (pinfunction "1_1") (pintype "input"))
      (node (ref "C23") (pin "1") (pinfunction "1_1") (pintype "input"))
      (node (ref "C24") (pin "1") (pinfunction "1_1") (pintype "input"))
      (node (ref "C25") (pin "1") (pinfunction "1_1") (pintype "input"))
      (node (ref "C29") (pin "2") (pinfunction "2_2") (pintype "unspecified"))
      (node (ref "C3") (pin "1") (pinfunction "1_1") (pintype "input"))
      (node (ref "C34") (pin "2") (pinfunction "2_2") (pintype "unspecified"))
      (node (ref "C35") (pin "1") (pinfunction "1_1") (pintype "input"))
      (node (ref "C36") (pin "1") (pinfunction "1_1") (pintype "unspecified"))
      (node (ref "C37") (pin "1") (pinfunction "1_1") (pintype "unspecified"))
      (node (ref "C38") (pin "1") (pinfunction "1_1") (pintype "unspecified"))
      (node (ref "C39") (pin "1") (pinfunction "1_1") (pintype "input"))
      (node (ref "C4") (pin "1") (pinfunction "1_1") (pintype "input"))
      (node (ref "C40") (pin "2") (pinfunction "2_2") (pintype "unspecified"))
      (node (ref "C41") (pin "1") (pinfunction "1_1") (pintype "unspecified"))
      (node (ref "C42") (pin "1") (pinfunction "1_1") (pintype "unspecified"))
      (node (ref "C43") (pin "1") (pinfunction "1_1") (pintype "unspecified"))
      (node (ref "C45") (pin "1") (pinfunction "1_1") (pintype "unspecified"))
      (node (ref "C46") (pin "1") (pinfunction "1_1") (pintype "unspecified"))
      (node (ref "C5") (pin "1") (pinfunction "1_1") (pintype "input"))
      (node (ref "C6") (pin "1") (pinfunction "1_1") (pintype "input"))
      (node (ref "C7") (pin "1") (pinfunction "1_1") (pintype "input"))
      (node (ref "C9") (pin "1") (pinfunction "1_1") (pintype "unspecified"))
      (node (ref "D1") (pin "2") (pinfunction "2_2") (pintype "unspecified"))
      (node (ref "D10") (pin "3") (pinfunction "GND_3") (pintype "unspecified"))
      (node (ref "D4") (pin "3") (pinfunction "GND_3") (pintype "unspecified"))
      (node (ref "D6") (pin "3") (pinfunction "GND_3") (pintype "unspecified"))
      (node (ref "D8") (pin "3") (pinfunction "GND_3") (pintype "unspecified"))
      (node (ref "D9") (pin "3") (pinfunction "GND_3") (pintype "unspecified"))
      (node (ref "H1") (pin "1") (pinfunction "1_1") (pintype "unspecified"))
      (node (ref "LED1") (pin "4") (pinfunction "K2_4") (pintype "unspecified"))
      (node (ref "R1") (pin "1") (pinfunction "1_1") (pintype "unspecified"))
      (node (ref "R10") (pin "1") (pinfunction "1_1") (pintype "input"))
      (node (ref "R11") (pin "1") (pinfunction "1_1") (pintype "input"))
      (node (ref "R3") (pin "1") (pinfunction "1_1") (pintype "unspecified"))
      (node (ref "R4") (pin "1") (pinfunction "1_1") (pintype "input"))
      (node (ref "SW3") (pin "2") (pinfunction "2_2") (pintype "unspecified"))
      (node (ref "SWD") (pin "4") (pinfunction "4_4") (pintype "unspecified"))
      (node (ref "U1") (pin "31") (pinfunction "RESV1_31") (pintype "unspecified"))
      (node (ref "U1") (pin "33") (pinfunction "DGND_33") (pintype "unspecified"))
      (node (ref "U1") (pin "49") (pinfunction "DGND_49") (pintype "unspecified"))
      (node (ref "U1") (pin "51") (pinfunction "DGND_51") (pintype "unspecified"))
      (node (ref "U1") (pin "60") (pinfunction "BIASREF_60") (pintype "unspecified"))
      (node (ref "U10") (pin "2") (pinfunction "GND_2") (pintype "unspecified"))
      (node (ref "U11") (pin "1") (pinfunction "1_1") (pintype "unspecified"))
      (node (ref "U11") (pin "2") (pinfunction "2_2") (pintype "unspecified"))
      (node (ref "U11") (pin "3") (pinfunction "3_3") (pintype "unspecified"))
      (node (ref "U11") (pin "4") (pinfunction "4_4") (pintype "unspecified"))
      (node (ref "U12") (pin "1") (pinfunction "1_1") (pintype "unspecified"))
      (node (ref "U12") (pin "2") (pinfunction "2_2") (pintype "unspecified"))
      (node (ref "U12") (pin "3") (pinfunction "3_3") (pintype "unspecified"))
      (node (ref "U12") (pin "4") (pinfunction "4_4") (pintype "unspecified"))
      (node (ref "U13") (pin "1") (pinfunction "1_1") (pintype "unspecified"))
      (node (ref "U13") (pin "2") (pinfunction "2_2") (pintype "unspecified"))
      (node (ref "U13") (pin "3") (pinfunction "3_3") (pintype "unspecified"))
      (node (ref "U13") (pin "4") (pinfunction "4_4") (pintype "unspecified"))
      (node (ref "U14") (pin "1") (pinfunction "1_1") (pintype "unspecified"))
      (node (ref "U14") (pin "2") (pinfunction "2_2") (pintype "unspecified"))
      (node (ref "U14") (pin "3") (pinfunction "3_3") (pintype "unspecified"))
      (node (ref "U14") (pin "4") (pinfunction "4_4") (pintype "unspecified"))
      (node (ref "U15") (pin "1") (pinfunction "1_1") (pintype "unspecified"))
      (node (ref "U15") (pin "2") (pinfunction "2_2") (pintype "unspecified"))
      (node (ref "U15") (pin "3") (pinfunction "3_3") (pintype "unspecified"))
      (node (ref "U15") (pin "4") (pinfunction "4_4") (pintype "unspecified"))
      (node (ref "U16") (pin "1") (pinfunction "1_1") (pintype "unspecified"))
      (node (ref "U16") (pin "2") (pinfunction "2_2") (pintype "unspecified"))
      (node (ref "U17") (pin "1") (pinfunction "1_1") (pintype "unspecified"))
      (node (ref "U17") (pin "2") (pinfunction "2_2") (pintype "unspecified"))
      (node (ref "U2") (pin "1") (pinfunction "1_1") (pintype "unspecified"))
      (node (ref "U2") (pin "2") (pinfunction "2_2") (pintype "unspecified"))
      (node (ref "U3") (pin "10") (pinfunction "VSS_10") (pintype "unspecified"))
      (node (ref "U3") (pin "26") (pinfunction "VSS_26") (pintype "unspecified"))
      (node (ref "U3") (pin "49") (pinfunction "VSS_49") (pintype "unspecified"))
      (node (ref "U3") (pin "74") (pinfunction "VSS_74") (pintype "unspecified"))
      (node (ref "U3") (pin "99") (pinfunction "VSS_99") (pintype "unspecified"))
      (node (ref "U4") (pin "2") (pinfunction "GND_2") (pintype "unspecified"))
      (node (ref "U5") (pin "2") (pinfunction "GND_2") (pintype "unspecified"))
      (node (ref "U6") (pin "2") (pinfunction "GND_2") (pintype "unspecified"))
      (node (ref "U7") (pin "2") (pinfunction "GND_2") (pintype "unspecified"))
      (node (ref "U8") (pin "1") (pinfunction "GND_1") (pintype "unspecified"))
      (node (ref "U9") (pin "1") (pinfunction "GND_1") (pintype "passive"))
      (node (ref "USART1") (pin "3") (pinfunction "3_3") (pintype "unspecified"))
      (node (ref "USB1") (pin "1") (pinfunction "GND_1") (pintype "unspecified"))
      (node (ref "USB1") (pin "2") (pinfunction "GND_2") (pintype "unspecified"))
      (node (ref "USB1") (pin "3") (pinfunction "GND_3") (pintype "unspecified"))
      (node (ref "USB1") (pin "4") (pinfunction "GND_4") (pintype "unspecified"))
      (node (ref "USB1") (pin "A12") (pinfunction "GND_A12") (pintype "unspecified"))
      (node (ref "USB1") (pin "B12") (pinfunction "GND_B12") (pintype "unspecified"))
      (node (ref "X1") (pin "2") (pinfunction "GND_2") (pintype "input"))
      (node (ref "X1") (pin "4") (pinfunction "GND_4") (pintype "input"))
    )
    (net (code "72") (name "Net-(LED1-A1)") (class "Default")
      (node (ref "LED1") (pin "1") (pinfunction "A1_1") (pintype "unspecified"))
      (node (ref "R2") (pin "1") (pinfunction "1_1") (pintype "unspecified"))
    )
    (net (code "73") (name "Net-(LED1-K1)") (class "Default")
      (node (ref "LED1") (pin "3") (pinfunction "K1_3") (pintype "unspecified"))
      (node (ref "U4") (pin "1") (pinfunction "CHRG_1") (pintype "unspecified"))
    )
    (net (code "74") (name "Net-(LED2-+)") (class "Default")
      (node (ref "LED2") (pin "2") (pinfunction "+_2") (pintype "unspecified"))
      (node (ref "R13") (pin "1") (pinfunction "1_1") (pintype "input"))
    )
    (net (code "75") (name "Net-(R7-Pad2)") (class "Default")
      (node (ref "R7") (pin "2") (pinfunction "2_2") (pintype "input"))
      (node (ref "SWD") (pin "2") (pinfunction "2_2") (pintype "unspecified"))
    )
    (net (code "76") (name "Net-(R8-Pad2)") (class "Default")
      (node (ref "R8") (pin "2") (pinfunction "2_2") (pintype "input"))
      (node (ref "SWD") (pin "3") (pinfunction "3_3") (pintype "unspecified"))
    )
    (net (code "77") (name "Net-(RN5-Pad5)") (class "Default")
      (node (ref "RN5") (pin "5") (pinfunction "5_5") (pintype "input"))
      (node (ref "U15") (pin "8") (pinfunction "8_8") (pintype "unspecified"))
    )
    (net (code "78") (name "Net-(U1-BIASIN)") (class "Default")
      (node (ref "C44") (pin "2") (pinfunction "2_2") (pintype "unspecified"))
      (node (ref "R15") (pin "1") (pinfunction "1_1") (pintype "unspecified"))
      (node (ref "U1") (pin "62") (pinfunction "BIASIN_62") (pintype "unspecified"))
      (node (ref "U1") (pin "63") (pinfunction "BIASOUT_63") (pintype "unspecified"))
    )
    (net (code "79") (name "Net-(U1-BIASINV)") (class "Default")
      (node (ref "BIAS_INV") (pin "2") (pinfunction "2_2") (pintype "input"))
      (node (ref "U1") (pin "61") (pinfunction "BIASINV_61") (pintype "unspecified"))
    )
    (net (code "80") (name "Net-(U1-DAISY_IN)") (class "Default")
      (node (ref "R3") (pin "2") (pinfunction "2_2") (pintype "unspecified"))
      (node (ref "U1") (pin "41") (pinfunction "DAISY_IN_41") (pintype "unspecified"))
    )
    (net (code "81") (name "Net-(U1-PWDN#)") (class "Default")
      (node (ref "R12") (pin "2") (pinfunction "2_2") (pintype "input"))
      (node (ref "U1") (pin "35") (pinfunction "PWDN#_35") (pintype "unspecified"))
    )
    (net (code "82") (name "Net-(U1-VCAP1)") (class "Default")
      (node (ref "C27") (pin "2") (pinfunction "2_2") (pintype "unspecified"))
      (node (ref "U1") (pin "28") (pinfunction "VCAP1_28") (pintype "unspecified"))
    )
    (net (code "83") (name "Net-(U1-VCAP2)") (class "Default")
      (node (ref "C30") (pin "2") (pinfunction "2_2") (pintype "input"))
      (node (ref "U1") (pin "30") (pinfunction "VCAP2_30") (pintype "unspecified"))
    )
    (net (code "84") (name "Net-(U1-VCAP3)") (class "Default")
      (node (ref "C31") (pin "1") (pinfunction "1_1") (pintype "input"))
      (node (ref "C32") (pin "1") (pinfunction "1_1") (pintype "input"))
      (node (ref "U1") (pin "55") (pinfunction "VCAP3_55") (pintype "unspecified"))
    )
    (net (code "85") (name "Net-(U1-VCAP4)") (class "Default")
      (node (ref "C28") (pin "2") (pinfunction "2_2") (pintype "input"))
      (node (ref "U1") (pin "26") (pinfunction "VCAP4_26") (pintype "unspecified"))
    )
    (net (code "86") (name "Net-(U1-VREFP)") (class "Default")
      (node (ref "C26") (pin "1") (pinfunction "1_1") (pintype "input"))
      (node (ref "C33") (pin "1") (pinfunction "1_1") (pintype "unspecified"))
      (node (ref "U1") (pin "24") (pinfunction "VREFP_24") (pintype "unspecified"))
    )
    (net (code "87") (name "Net-(U4-PROG)") (class "Default")
      (node (ref "R1") (pin "2") (pinfunction "2_2") (pintype "unspecified"))
      (node (ref "U4") (pin "5") (pinfunction "PROG_5") (pintype "unspecified"))
    )
    (net (code "88") (name "Net-(U8-CAP+)") (class "Default")
      (node (ref "C8") (pin "2") (pinfunction "2_2") (pintype "unspecified"))
      (node (ref "U8") (pin "6") (pinfunction "CAP+_6") (pintype "unspecified"))
    )
    (net (code "89") (name "Net-(U8-CAP-)") (class "Default")
      (node (ref "C8") (pin "1") (pinfunction "1_1") (pintype "unspecified"))
      (node (ref "U8") (pin "3") (pinfunction "CAP-_3") (pintype "unspecified"))
    )
    (net (code "90") (name "Net-(U9-NR{slash}FB)") (class "Default")
      (node (ref "C10") (pin "2") (pinfunction "2_2") (pintype "input"))
      (node (ref "U9") (pin "4") (pinfunction "NR/FB_4") (pintype "unspecified"))
    )
    (net (code "91") (name "unconnected-(BIAS_INV-Pad1)") (class "Default")
      (node (ref "BIAS_INV") (pin "1") (pinfunction "1_1") (pintype "input+no_connect"))
    )
    (net (code "92") (name "unconnected-(D4-NC-Pad6)") (class "Default")
      (node (ref "D4") (pin "6") (pinfunction "NC_6") (pintype "unspecified+no_connect"))
    )
    (net (code "93") (name "unconnected-(D6-NC-Pad6)") (class "Default")
      (node (ref "D6") (pin "6") (pinfunction "NC_6") (pintype "unspecified+no_connect"))
    )
    (net (code "94") (name "unconnected-(D7-+-Pad2)") (class "Default")
      (node (ref "D7") (pin "2") (pinfunction "+_2") (pintype "unspecified+no_connect"))
    )
    (net (code "95") (name "unconnected-(D8-NC-Pad6)") (class "Default")
      (node (ref "D8") (pin "6") (pinfunction "NC_6") (pintype "unspecified+no_connect"))
    )
    (net (code "96") (name "unconnected-(D9-NC-Pad6)") (class "Default")
      (node (ref "D9") (pin "6") (pinfunction "NC_6") (pintype "unspecified+no_connect"))
    )
    (net (code "97") (name "unconnected-(D10-NC-Pad6)") (class "Default")
      (node (ref "D10") (pin "6") (pinfunction "NC_6") (pintype "unspecified+no_connect"))
    )
    (net (code "98") (name "unconnected-(RN5-Pad4)") (class "Default")
      (node (ref "RN5") (pin "4") (pinfunction "4_4") (pintype "input"))
    )
    (net (code "99") (name "unconnected-(SW1-Pad1)") (class "Default")
      (node (ref "SW1") (pin "1") (pinfunction "1_1") (pintype "unspecified+no_connect"))
    )
    (net (code "100") (name "unconnected-(SW1-Pad4)") (class "Default")
      (node (ref "SW1") (pin "4") (pinfunction "4_4") (pintype "unspecified+no_connect"))
    )
    (net (code "101") (name "unconnected-(SW1-Pad5)") (class "Default")
      (node (ref "SW1") (pin "5") (pinfunction "5_5") (pintype "unspecified+no_connect"))
    )
    (net (code "102") (name "unconnected-(SW1-Pad6)") (class "Default")
      (node (ref "SW1") (pin "6") (pinfunction "6_6") (pintype "unspecified+no_connect"))
    )
    (net (code "103") (name "unconnected-(SW1-Pad7)") (class "Default")
      (node (ref "SW1") (pin "7") (pinfunction "7_7") (pintype "unspecified+no_connect"))
    )
    (net (code "104") (name "unconnected-(U1-CLK-Pad37)") (class "Default")
      (node (ref "U1") (pin "37") (pinfunction "CLK_37") (pintype "unspecified+no_connect"))
    )
    (net (code "105") (name "unconnected-(U1-GPIO1-Pad42)") (class "Default")
      (node (ref "U1") (pin "42") (pinfunction "GPIO1_42") (pintype "unspecified+no_connect"))
    )
    (net (code "106") (name "unconnected-(U1-GPIO2-Pad44)") (class "Default")
      (node (ref "U1") (pin "44") (pinfunction "GPIO2_44") (pintype "unspecified+no_connect"))
    )
    (net (code "107") (name "unconnected-(U1-GPIO3-Pad45)") (class "Default")
      (node (ref "U1") (pin "45") (pinfunction "GPIO3_45") (pintype "unspecified+no_connect"))
    )
    (net (code "108") (name "unconnected-(U1-GPIO4-Pad46)") (class "Default")
      (node (ref "U1") (pin "46") (pinfunction "GPIO4_46") (pintype "unspecified+no_connect"))
    )
    (net (code "109") (name "unconnected-(U1-NC-Pad27)") (class "Default")
      (node (ref "U1") (pin "27") (pinfunction "NC_27") (pintype "unspecified+no_connect"))
    )
    (net (code "110") (name "unconnected-(U1-NC-Pad29)") (class "Default")
      (node (ref "U1") (pin "29") (pinfunction "NC_29") (pintype "unspecified+no_connect"))
    )
    (net (code "111") (name "unconnected-(U1-RESERVED-Pad64)") (class "Default")
      (node (ref "U1") (pin "64") (pinfunction "RESERVED_64") (pintype "unspecified+no_connect"))
    )
    (net (code "112") (name "unconnected-(U3-PA0-Pad22)") (class "Default")
      (node (ref "U3") (pin "22") (pinfunction "PA0_22") (pintype "unspecified"))
    )
    (net (code "113") (name "unconnected-(U3-PA1-Pad23)") (class "Default")
      (node (ref "U3") (pin "23") (pinfunction "PA1_23") (pintype "unspecified"))
    )
    (net (code "114") (name "unconnected-(U3-PA2-Pad24)") (class "Default")
      (node (ref "U3") (pin "24") (pinfunction "PA2_24") (pintype "unspecified"))
    )
    (net (code "115") (name "unconnected-(U3-PA3-Pad25)") (class "Default")
      (node (ref "U3") (pin "25") (pinfunction "PA3_25") (pintype "unspecified"))
    )
    (net (code "116") (name "unconnected-(U3-PA4-Pad28)") (class "Default")
      (node (ref "U3") (pin "28") (pinfunction "PA4_28") (pintype "unspecified"))
    )
    (net (code "117") (name "unconnected-(U3-PA5-Pad29)") (class "Default")
      (node (ref "U3") (pin "29") (pinfunction "PA5_29") (pintype "unspecified"))
    )
    (net (code "118") (name "unconnected-(U3-PA6-Pad30)") (class "Default")
      (node (ref "U3") (pin "30") (pinfunction "PA6_30") (pintype "unspecified"))
    )
    (net (code "119") (name "unconnected-(U3-PA7-Pad31)") (class "Default")
      (node (ref "U3") (pin "31") (pinfunction "PA7_31") (pintype "unspecified"))
    )
    (net (code "120") (name "unconnected-(U3-PA8-Pad67)") (class "Default")
      (node (ref "U3") (pin "67") (pinfunction "PA8_67") (pintype "unspecified"))
    )
    (net (code "121") (name "unconnected-(U3-PA11-Pad70)") (class "Default")
      (node (ref "U3") (pin "70") (pinfunction "PA11_70") (pintype "unspecified"))
    )
    (net (code "122") (name "unconnected-(U3-PA12-Pad71)") (class "Default")
      (node (ref "U3") (pin "71") (pinfunction "PA12_71") (pintype "unspecified"))
    )
    (net (code "123") (name "unconnected-(U3-PA15-Pad77)") (class "Default")
      (node (ref "U3") (pin "77") (pinfunction "PA15_77") (pintype "unspecified"))
    )
    (net (code "124") (name "unconnected-(U3-PB0-Pad34)") (class "Default")
      (node (ref "U3") (pin "34") (pinfunction "PB0_34") (pintype "unspecified"))
    )
    (net (code "125") (name "unconnected-(U3-PB1-Pad35)") (class "Default")
      (node (ref "U3") (pin "35") (pinfunction "PB1_35") (pintype "unspecified"))
    )
    (net (code "126") (name "unconnected-(U3-PB2-Pad36)") (class "Default")
      (node (ref "U3") (pin "36") (pinfunction "PB2_36") (pintype "unspecified"))
    )
    (net (code "127") (name "unconnected-(U3-PB3-Pad89)") (class "Default")
      (node (ref "U3") (pin "89") (pinfunction "PB3_89") (pintype "unspecified"))
    )
    (net (code "128") (name "unconnected-(U3-PB4-Pad90)") (class "Default")
      (node (ref "U3") (pin "90") (pinfunction "PB4_90") (pintype "unspecified"))
    )
    (net (code "129") (name "unconnected-(U3-PB5-Pad91)") (class "Default")
      (node (ref "U3") (pin "91") (pinfunction "PB5_91") (pintype "unspecified"))
    )
    (net (code "130") (name "unconnected-(U3-PB6-Pad92)") (class "Default")
      (node (ref "U3") (pin "92") (pinfunction "PB6_92") (pintype "unspecified"))
    )
    (net (code "131") (name "unconnected-(U3-PB7-Pad93)") (class "Default")
      (node (ref "U3") (pin "93") (pinfunction "PB7_93") (pintype "unspecified"))
    )
    (net (code "132") (name "unconnected-(U3-PB8-Pad95)") (class "Default")
      (node (ref "U3") (pin "95") (pinfunction "PB8_95") (pintype "unspecified"))
    )
    (net (code "133") (name "unconnected-(U3-PB9-Pad96)") (class "Default")
      (node (ref "U3") (pin "96") (pinfunction "PB9_96") (pintype "unspecified"))
    )
    (net (code "134") (name "unconnected-(U3-PB10-Pad46)") (class "Default")
      (node (ref "U3") (pin "46") (pinfunction "PB10_46") (pintype "unspecified"))
    )
    (net (code "135") (name "unconnected-(U3-PB11-Pad47)") (class "Default")
      (node (ref "U3") (pin "47") (pinfunction "PB11_47") (pintype "unspecified"))
    )
    (net (code "136") (name "unconnected-(U3-PB12-Pad51)") (class "Default")
      (node (ref "U3") (pin "51") (pinfunction "PB12_51") (pintype "unspecified"))
    )
    (net (code "137") (name "unconnected-(U3-PB13-Pad52)") (class "Default")
      (node (ref "U3") (pin "52") (pinfunction "PB13_52") (pintype "unspecified"))
    )
    (net (code "138") (name "unconnected-(U3-PB14-Pad53)") (class "Default")
      (node (ref "U3") (pin "53") (pinfunction "PB14_53") (pintype "unspecified"))
    )
    (net (code "139") (name "unconnected-(U3-PB15-Pad54)") (class "Default")
      (node (ref "U3") (pin "54") (pinfunction "PB15_54") (pintype "unspecified"))
    )
    (net (code "140") (name "unconnected-(U3-PC0-Pad15)") (class "Default")
      (node (ref "U3") (pin "15") (pinfunction "PC0_15") (pintype "unspecified"))
    )
    (net (code "141") (name "unconnected-(U3-PC1-Pad16)") (class "Default")
      (node (ref "U3") (pin "16") (pinfunction "PC1_16") (pintype "unspecified"))
    )
    (net (code "142") (name "unconnected-(U3-PC2_C-Pad17)") (class "Default")
      (node (ref "U3") (pin "17") (pinfunction "PC2_C_17") (pintype "unspecified"))
    )
    (net (code "143") (name "unconnected-(U3-PC3_C-Pad18)") (class "Default")
      (node (ref "U3") (pin "18") (pinfunction "PC3_C_18") (pintype "unspecified"))
    )
    (net (code "144") (name "unconnected-(U3-PC4-Pad32)") (class "Default")
      (node (ref "U3") (pin "32") (pinfunction "PC4_32") (pintype "unspecified"))
    )
    (net (code "145") (name "unconnected-(U3-PC5-Pad33)") (class "Default")
      (node (ref "U3") (pin "33") (pinfunction "PC5_33") (pintype "unspecified"))
    )
    (net (code "146") (name "unconnected-(U3-PC6-Pad63)") (class "Default")
      (node (ref "U3") (pin "63") (pinfunction "PC6_63") (pintype "unspecified"))
    )
    (net (code "147") (name "unconnected-(U3-PC7-Pad64)") (class "Default")
      (node (ref "U3") (pin "64") (pinfunction "PC7_64") (pintype "unspecified"))
    )
    (net (code "148") (name "unconnected-(U3-PC8-Pad65)") (class "Default")
      (node (ref "U3") (pin "65") (pinfunction "PC8_65") (pintype "unspecified"))
    )
    (net (code "149") (name "unconnected-(U3-PC9-Pad66)") (class "Default")
      (node (ref "U3") (pin "66") (pinfunction "PC9_66") (pintype "unspecified"))
    )
    (net (code "150") (name "unconnected-(U3-PC10-Pad78)") (class "Default")
      (node (ref "U3") (pin "78") (pinfunction "PC10_78") (pintype "unspecified"))
    )
    (net (code "151") (name "unconnected-(U3-PC11-Pad79)") (class "Default")
      (node (ref "U3") (pin "79") (pinfunction "PC11_79") (pintype "unspecified"))
    )
    (net (code "152") (name "unconnected-(U3-PC12-Pad80)") (class "Default")
      (node (ref "U3") (pin "80") (pinfunction "PC12_80") (pintype "unspecified"))
    )
    (net (code "153") (name "unconnected-(U3-PC14-OSC32_IN-Pad8)") (class "Default")
      (node (ref "U3") (pin "8") (pinfunction "PC14-OSC32_IN_8") (pintype "unspecified"))
    )
    (net (code "154") (name "unconnected-(U3-PC15-OSC32_OUT-Pad9)") (class "Default")
      (node (ref "U3") (pin "9") (pinfunction "PC15-OSC32_OUT_9") (pintype "unspecified"))
    )
    (net (code "155") (name "unconnected-(U3-PD0-Pad81)") (class "Default")
      (node (ref "U3") (pin "81") (pinfunction "PD0_81") (pintype "unspecified"))
    )
    (net (code "156") (name "unconnected-(U3-PD1-Pad82)") (class "Default")
      (node (ref "U3") (pin "82") (pinfunction "PD1_82") (pintype "unspecified"))
    )
    (net (code "157") (name "unconnected-(U3-PD2-Pad83)") (class "Default")
      (node (ref "U3") (pin "83") (pinfunction "PD2_83") (pintype "unspecified"))
    )
    (net (code "158") (name "unconnected-(U3-PD3-Pad84)") (class "Default")
      (node (ref "U3") (pin "84") (pinfunction "PD3_84") (pintype "unspecified"))
    )
    (net (code "159") (name "unconnected-(U3-PD4-Pad85)") (class "Default")
      (node (ref "U3") (pin "85") (pinfunction "PD4_85") (pintype "unspecified"))
    )
    (net (code "160") (name "unconnected-(U3-PD5-Pad86)") (class "Default")
      (node (ref "U3") (pin "86") (pinfunction "PD5_86") (pintype "unspecified"))
    )
    (net (code "161") (name "unconnected-(U3-PD6-Pad87)") (class "Default")
      (node (ref "U3") (pin "87") (pinfunction "PD6_87") (pintype "unspecified"))
    )
    (net (code "162") (name "unconnected-(U3-PD7-Pad88)") (class "Default")
      (node (ref "U3") (pin "88") (pinfunction "PD7_88") (pintype "unspecified"))
    )
    (net (code "163") (name "unconnected-(U3-PD8-Pad55)") (class "Default")
      (node (ref "U3") (pin "55") (pinfunction "PD8_55") (pintype "unspecified"))
    )
    (net (code "164") (name "unconnected-(U3-PD9-Pad56)") (class "Default")
      (node (ref "U3") (pin "56") (pinfunction "PD9_56") (pintype "unspecified"))
    )
    (net (code "165") (name "unconnected-(U3-PD10-Pad57)") (class "Default")
      (node (ref "U3") (pin "57") (pinfunction "PD10_57") (pintype "unspecified"))
    )
    (net (code "166") (name "unconnected-(U3-PD11-Pad58)") (class "Default")
      (node (ref "U3") (pin "58") (pinfunction "PD11_58") (pintype "unspecified"))
    )
    (net (code "167") (name "unconnected-(U3-PD12-Pad59)") (class "Default")
      (node (ref "U3") (pin "59") (pinfunction "PD12_59") (pintype "unspecified"))
    )
    (net (code "168") (name "unconnected-(U3-PD13-Pad60)") (class "Default")
      (node (ref "U3") (pin "60") (pinfunction "PD13_60") (pintype "unspecified"))
    )
    (net (code "169") (name "unconnected-(U3-PD14-Pad61)") (class "Default")
      (node (ref "U3") (pin "61") (pinfunction "PD14_61") (pintype "unspecified"))
    )
    (net (code "170") (name "unconnected-(U3-PD15-Pad62)") (class "Default")
      (node (ref "U3") (pin "62") (pinfunction "PD15_62") (pintype "unspecified"))
    )
    (net (code "171") (name "unconnected-(U3-PE0-Pad97)") (class "Default")
      (node (ref "U3") (pin "97") (pinfunction "PE0_97") (pintype "unspecified"))
    )
    (net (code "172") (name "unconnected-(U3-PE1-Pad98)") (class "Default")
      (node (ref "U3") (pin "98") (pinfunction "PE1_98") (pintype "unspecified"))
    )
    (net (code "173") (name "unconnected-(U3-PE2-Pad1)") (class "Default")
      (node (ref "U3") (pin "1") (pinfunction "PE2_1") (pintype "unspecified"))
    )
    (net (code "174") (name "unconnected-(U3-PE4-Pad3)") (class "Default")
      (node (ref "U3") (pin "3") (pinfunction "PE4_3") (pintype "unspecified"))
    )
    (net (code "175") (name "unconnected-(U3-PE5-Pad4)") (class "Default")
      (node (ref "U3") (pin "4") (pinfunction "PE5_4") (pintype "unspecified"))
    )
    (net (code "176") (name "unconnected-(U3-PE6-Pad5)") (class "Default")
      (node (ref "U3") (pin "5") (pinfunction "PE6_5") (pintype "unspecified"))
    )
    (net (code "177") (name "unconnected-(U3-PE7-Pad37)") (class "Default")
      (node (ref "U3") (pin "37") (pinfunction "PE7_37") (pintype "unspecified"))
    )
    (net (code "178") (name "unconnected-(U3-PE8-Pad38)") (class "Default")
      (node (ref "U3") (pin "38") (pinfunction "PE8_38") (pintype "unspecified"))
    )
    (net (code "179") (name "unconnected-(U3-PE9-Pad39)") (class "Default")
      (node (ref "U3") (pin "39") (pinfunction "PE9_39") (pintype "unspecified"))
    )
    (net (code "180") (name "unconnected-(U3-PE10-Pad40)") (class "Default")
      (node (ref "U3") (pin "40") (pinfunction "PE10_40") (pintype "unspecified"))
    )
    (net (code "181") (name "unconnected-(U3-PE11-Pad41)") (class "Default")
      (node (ref "U3") (pin "41") (pinfunction "PE11_41") (pintype "unspecified"))
    )
    (net (code "182") (name "unconnected-(U3-PE12-Pad42)") (class "Default")
      (node (ref "U3") (pin "42") (pinfunction "PE12_42") (pintype "unspecified"))
    )
    (net (code "183") (name "unconnected-(U3-PE13-Pad43)") (class "Default")
      (node (ref "U3") (pin "43") (pinfunction "PE13_43") (pintype "unspecified"))
    )
    (net (code "184") (name "unconnected-(U3-PE14-Pad44)") (class "Default")
      (node (ref "U3") (pin "44") (pinfunction "PE14_44") (pintype "unspecified"))
    )
    (net (code "185") (name "unconnected-(U3-PE15-Pad45)") (class "Default")
      (node (ref "U3") (pin "45") (pinfunction "PE15_45") (pintype "unspecified"))
    )
    (net (code "186") (name "unconnected-(U5-EP-Pad5)") (class "Default")
      (node (ref "U5") (pin "5") (pinfunction "EP_5") (pintype "unspecified+no_connect"))
    )
    (net (code "187") (name "unconnected-(U6-EP-Pad5)") (class "Default")
      (node (ref "U6") (pin "5") (pinfunction "EP_5") (pintype "unspecified+no_connect"))
    )
    (net (code "188") (name "unconnected-(U7-EP-Pad5)") (class "Default")
      (node (ref "U7") (pin "5") (pinfunction "EP_5") (pintype "unspecified+no_connect"))
    )
    (net (code "189") (name "unconnected-(U10-PAD-Pad5)") (class "Default")
      (node (ref "U10") (pin "5") (pinfunction "PAD_5") (pintype "unspecified+no_connect"))
    )
    (net (code "190") (name "unconnected-(USB1-CC1-PadA5)") (class "Default")
      (node (ref "USB1") (pin "A5") (pinfunction "CC1_A5") (pintype "unspecified+no_connect"))
    )
    (net (code "191") (name "unconnected-(USB1-CC2-PadB5)") (class "Default")
      (node (ref "USB1") (pin "B5") (pinfunction "CC2_B5") (pintype "unspecified+no_connect"))
    )
  )
)
